# shelves_v60.net
KiCad netlist of a schematic drawn in EAGLE
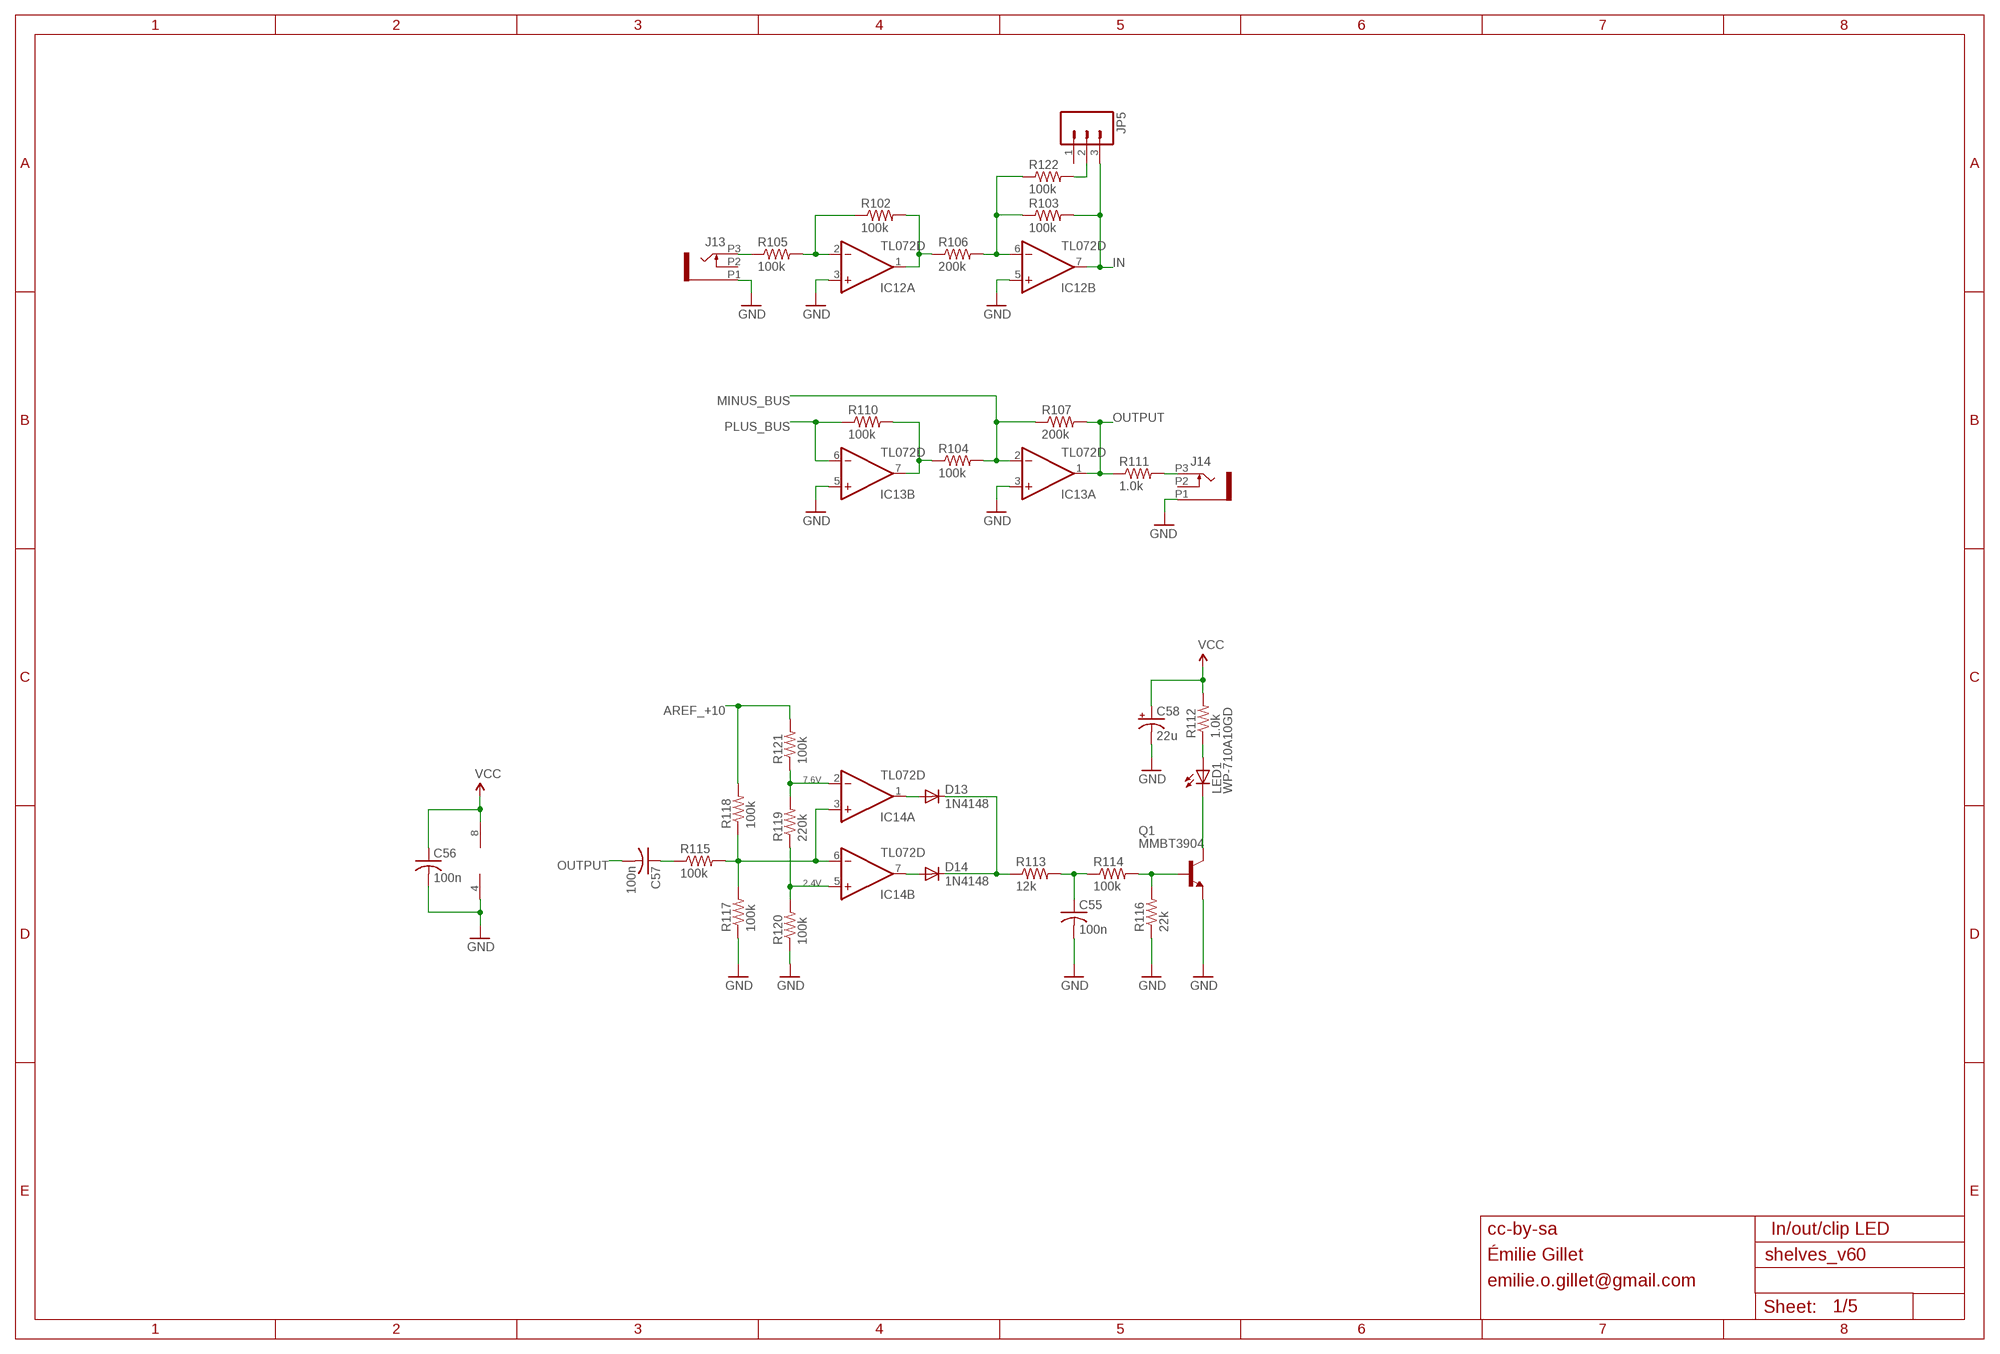
[diagram p0: schematic, sheet 1]
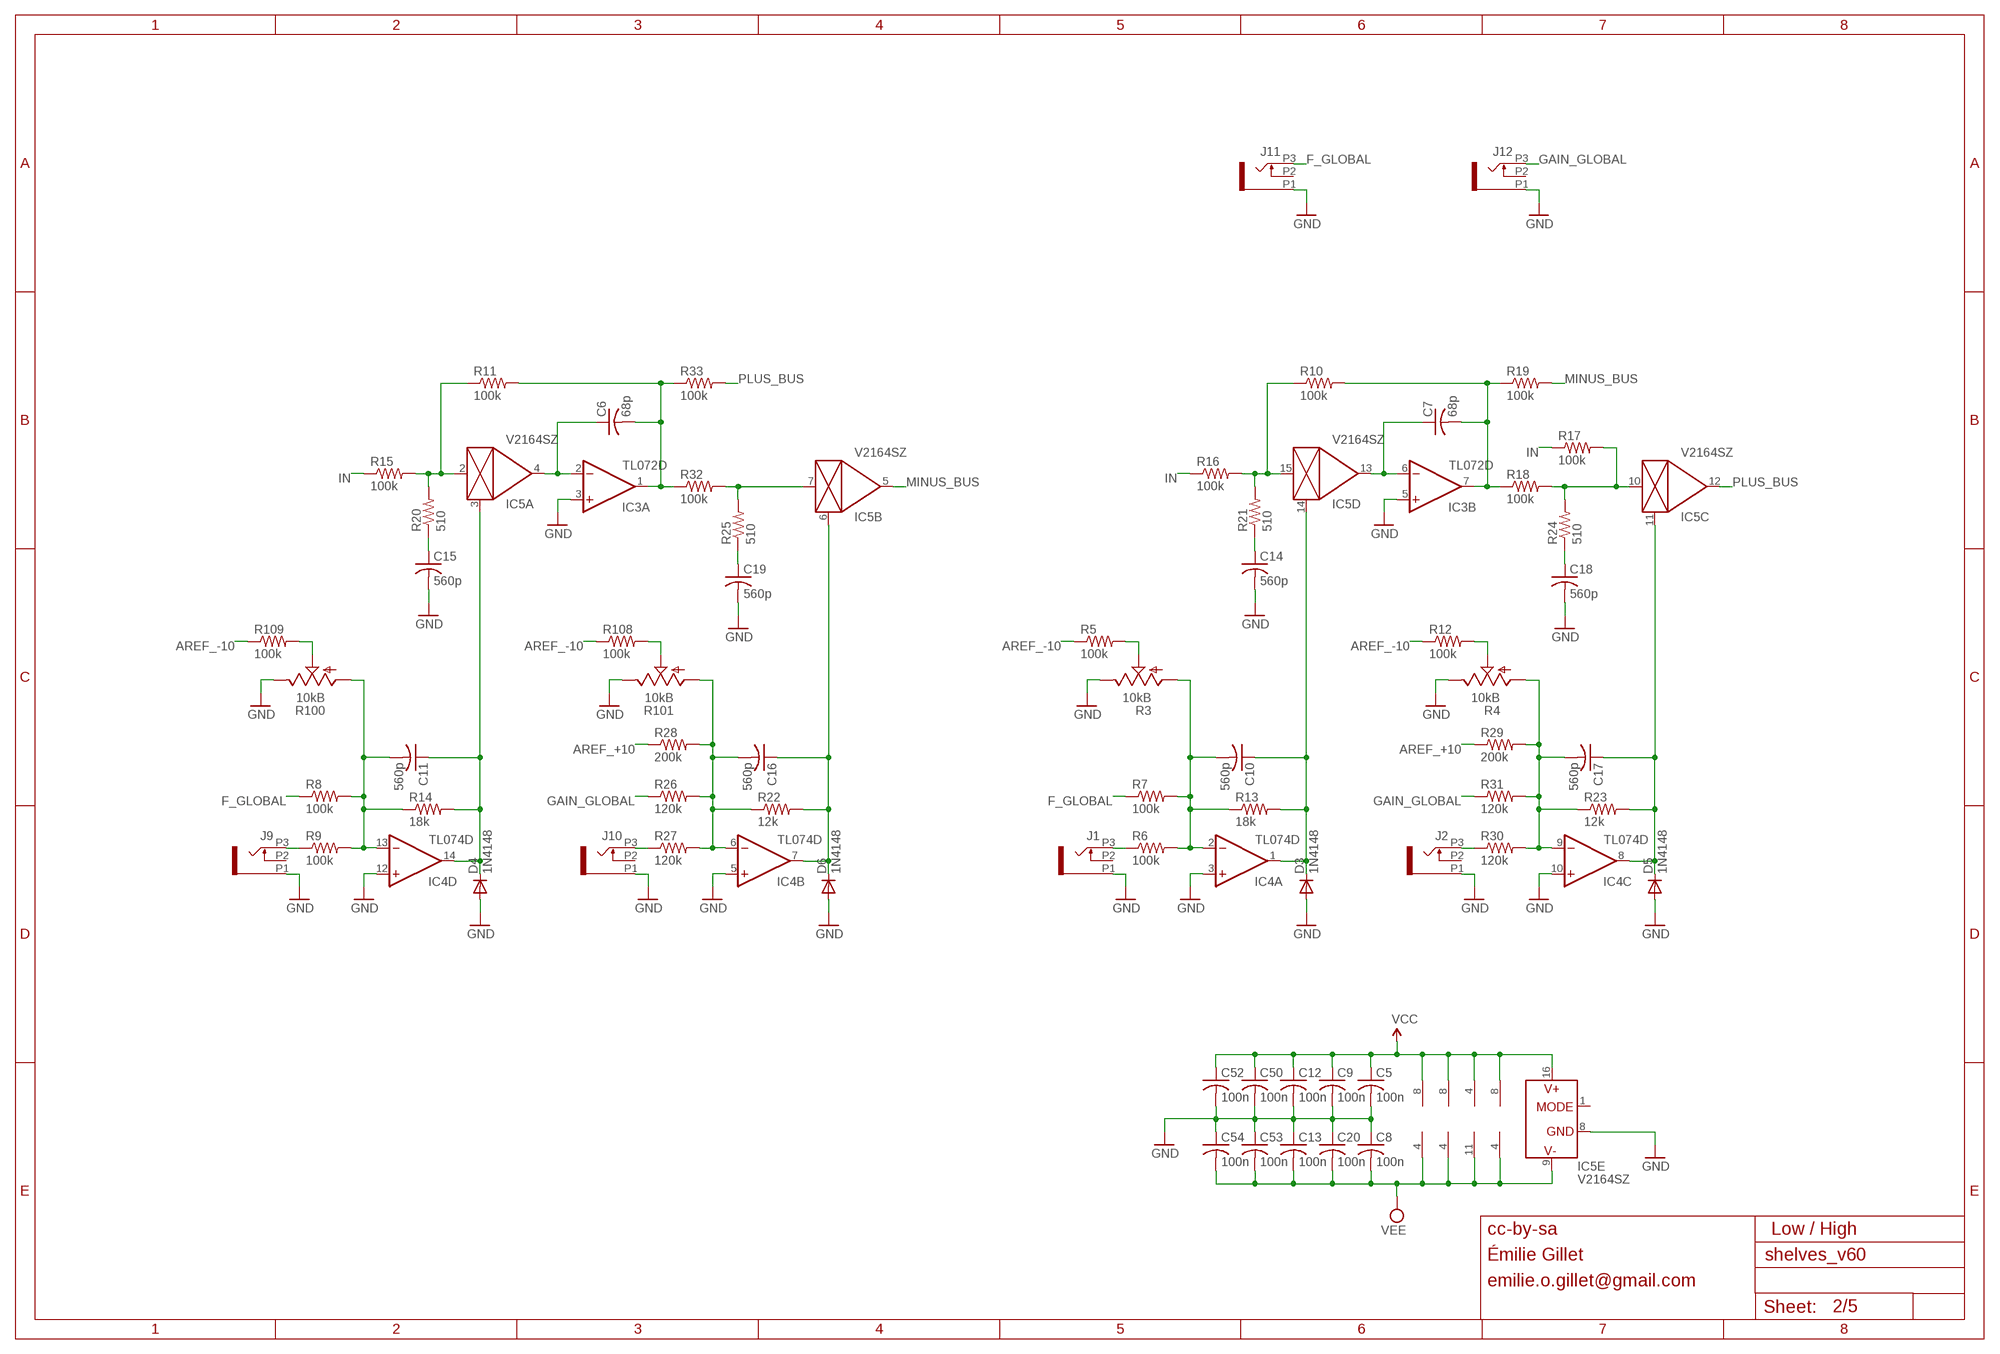
[diagram p1: schematic, sheet 2]
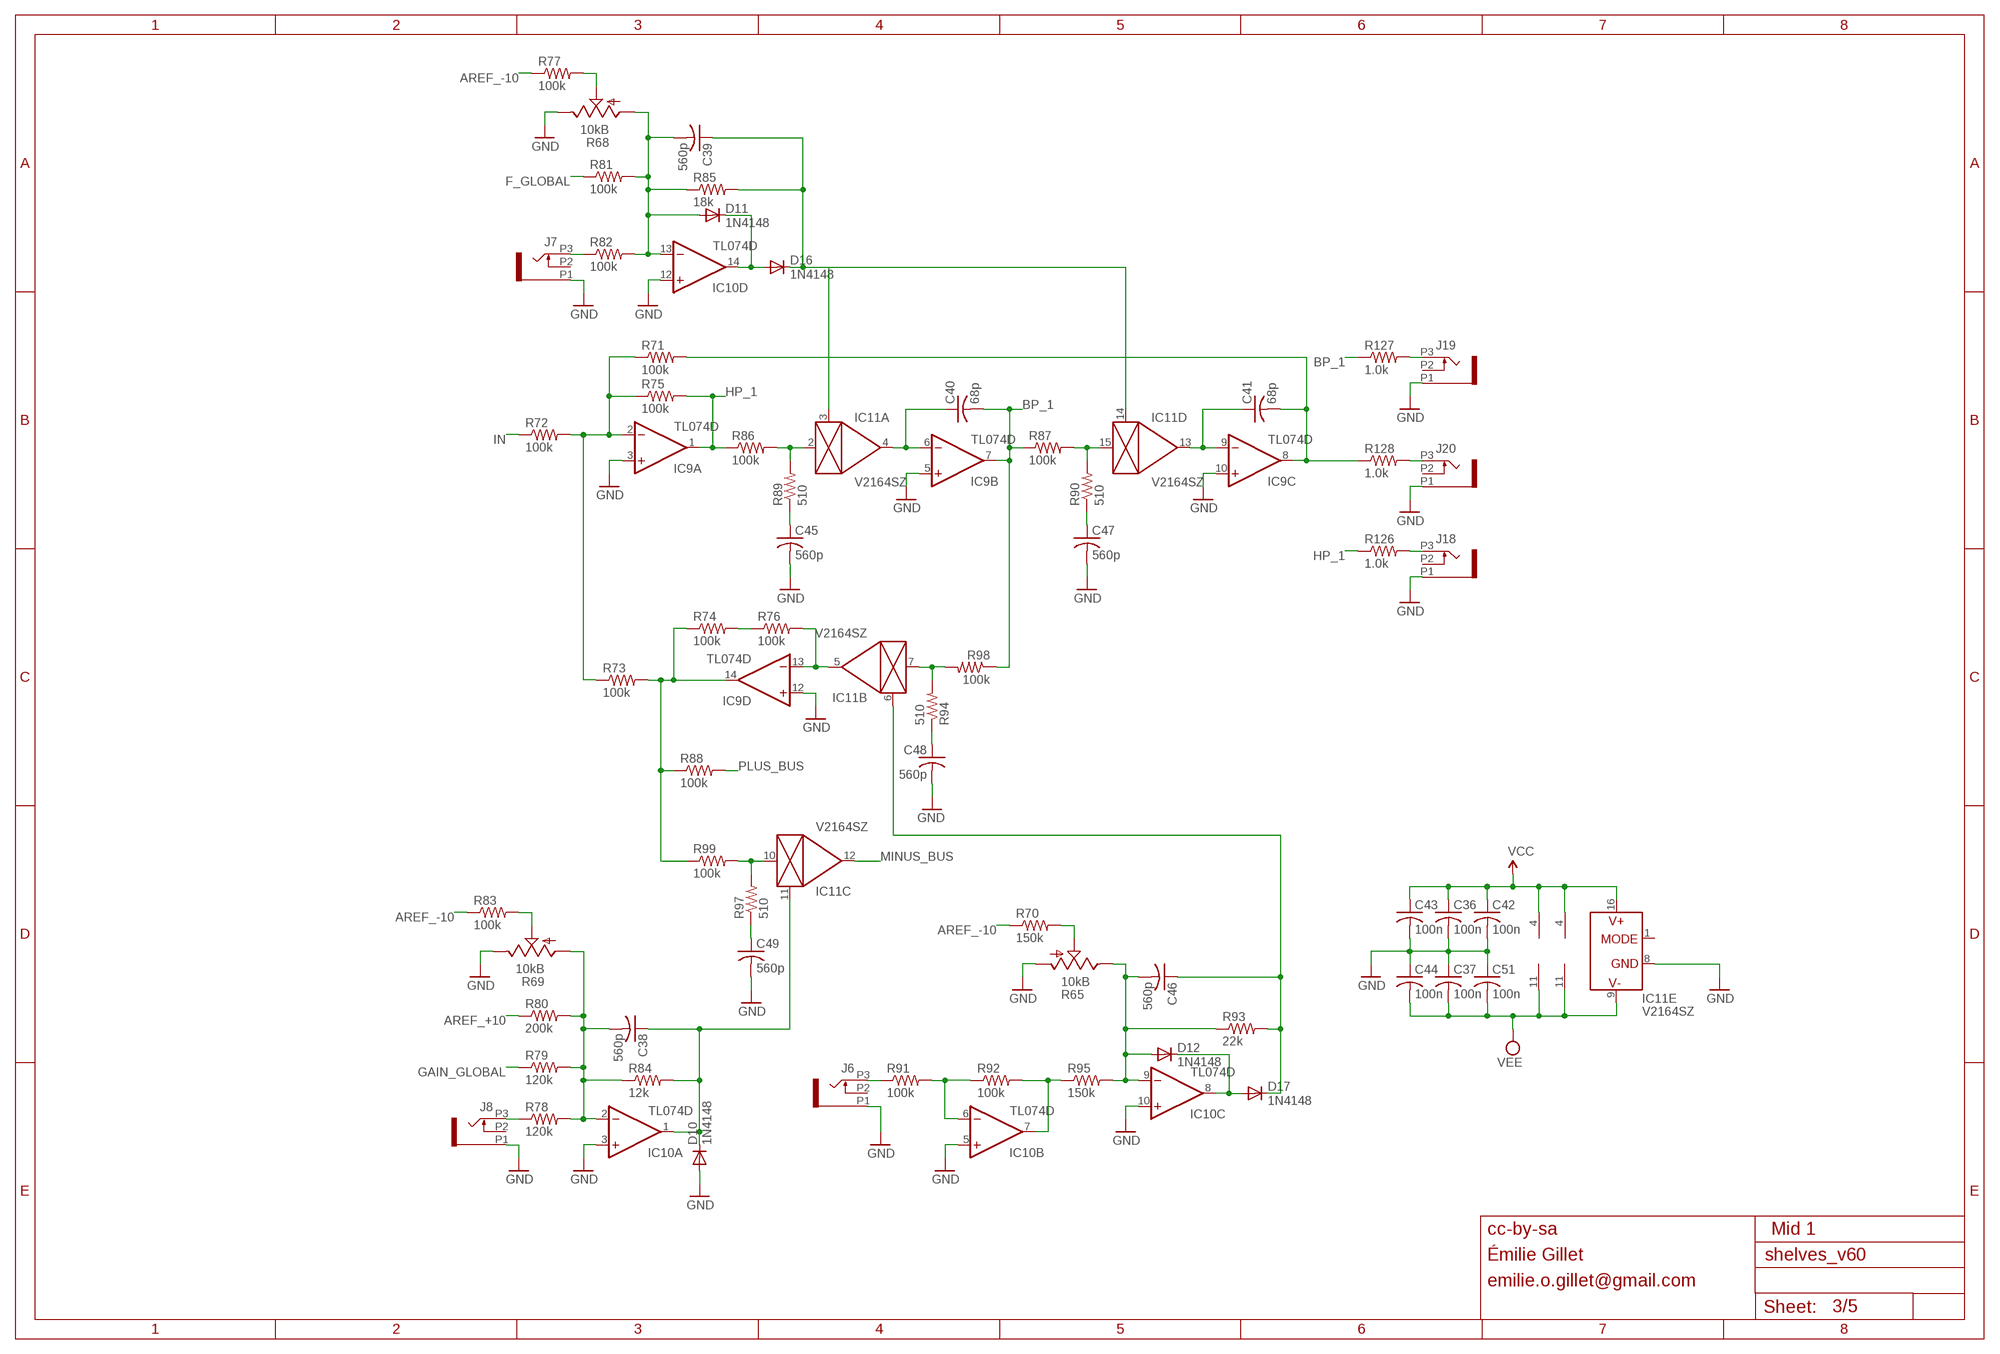
[diagram p2: schematic, sheet 3]
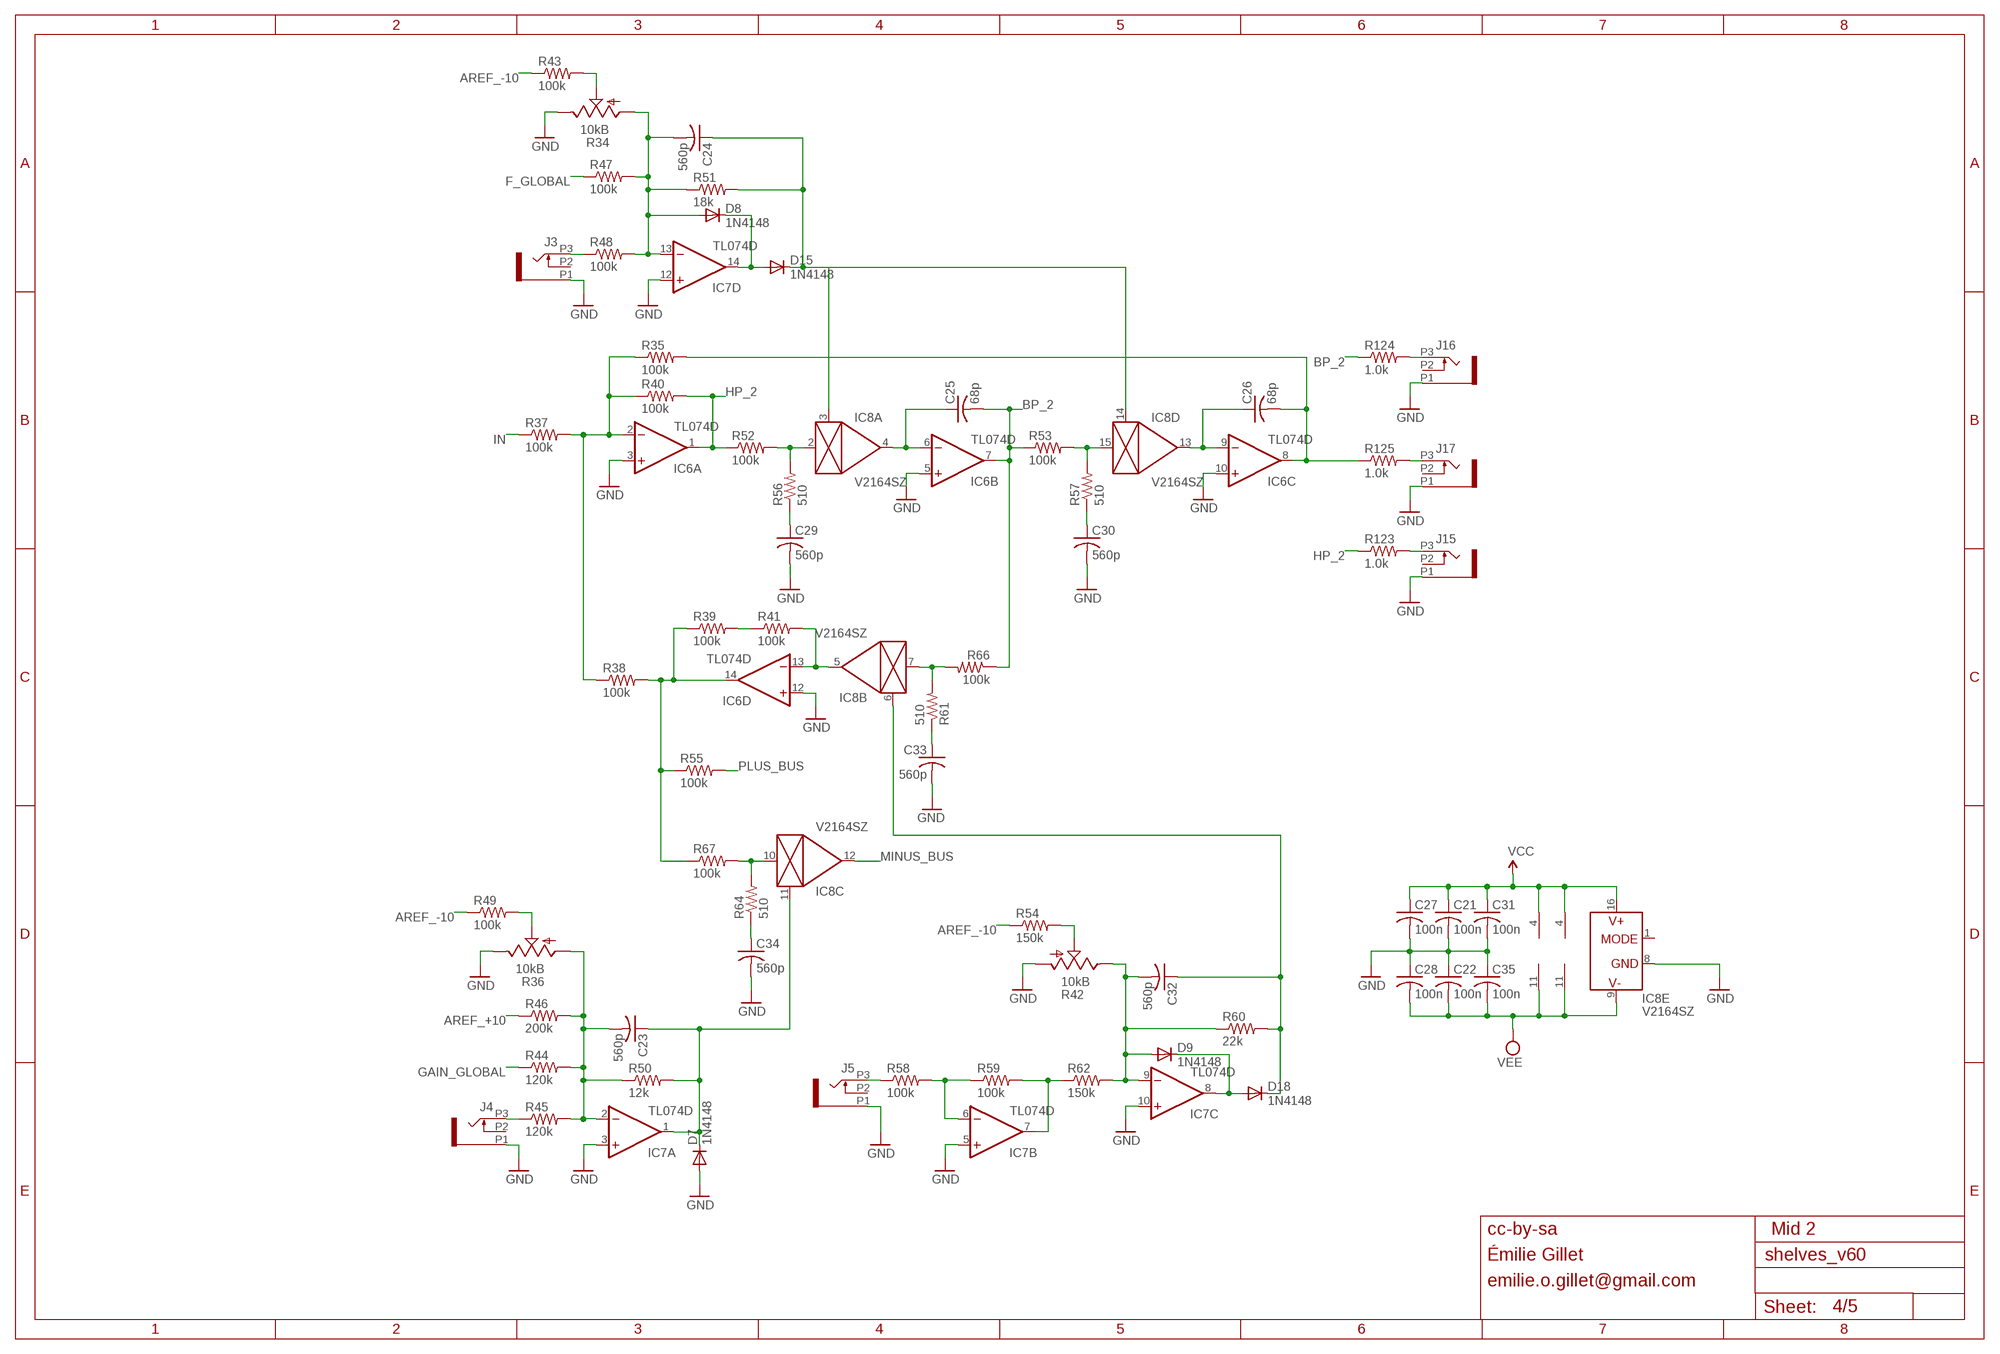
[diagram p3: schematic, sheet 4]
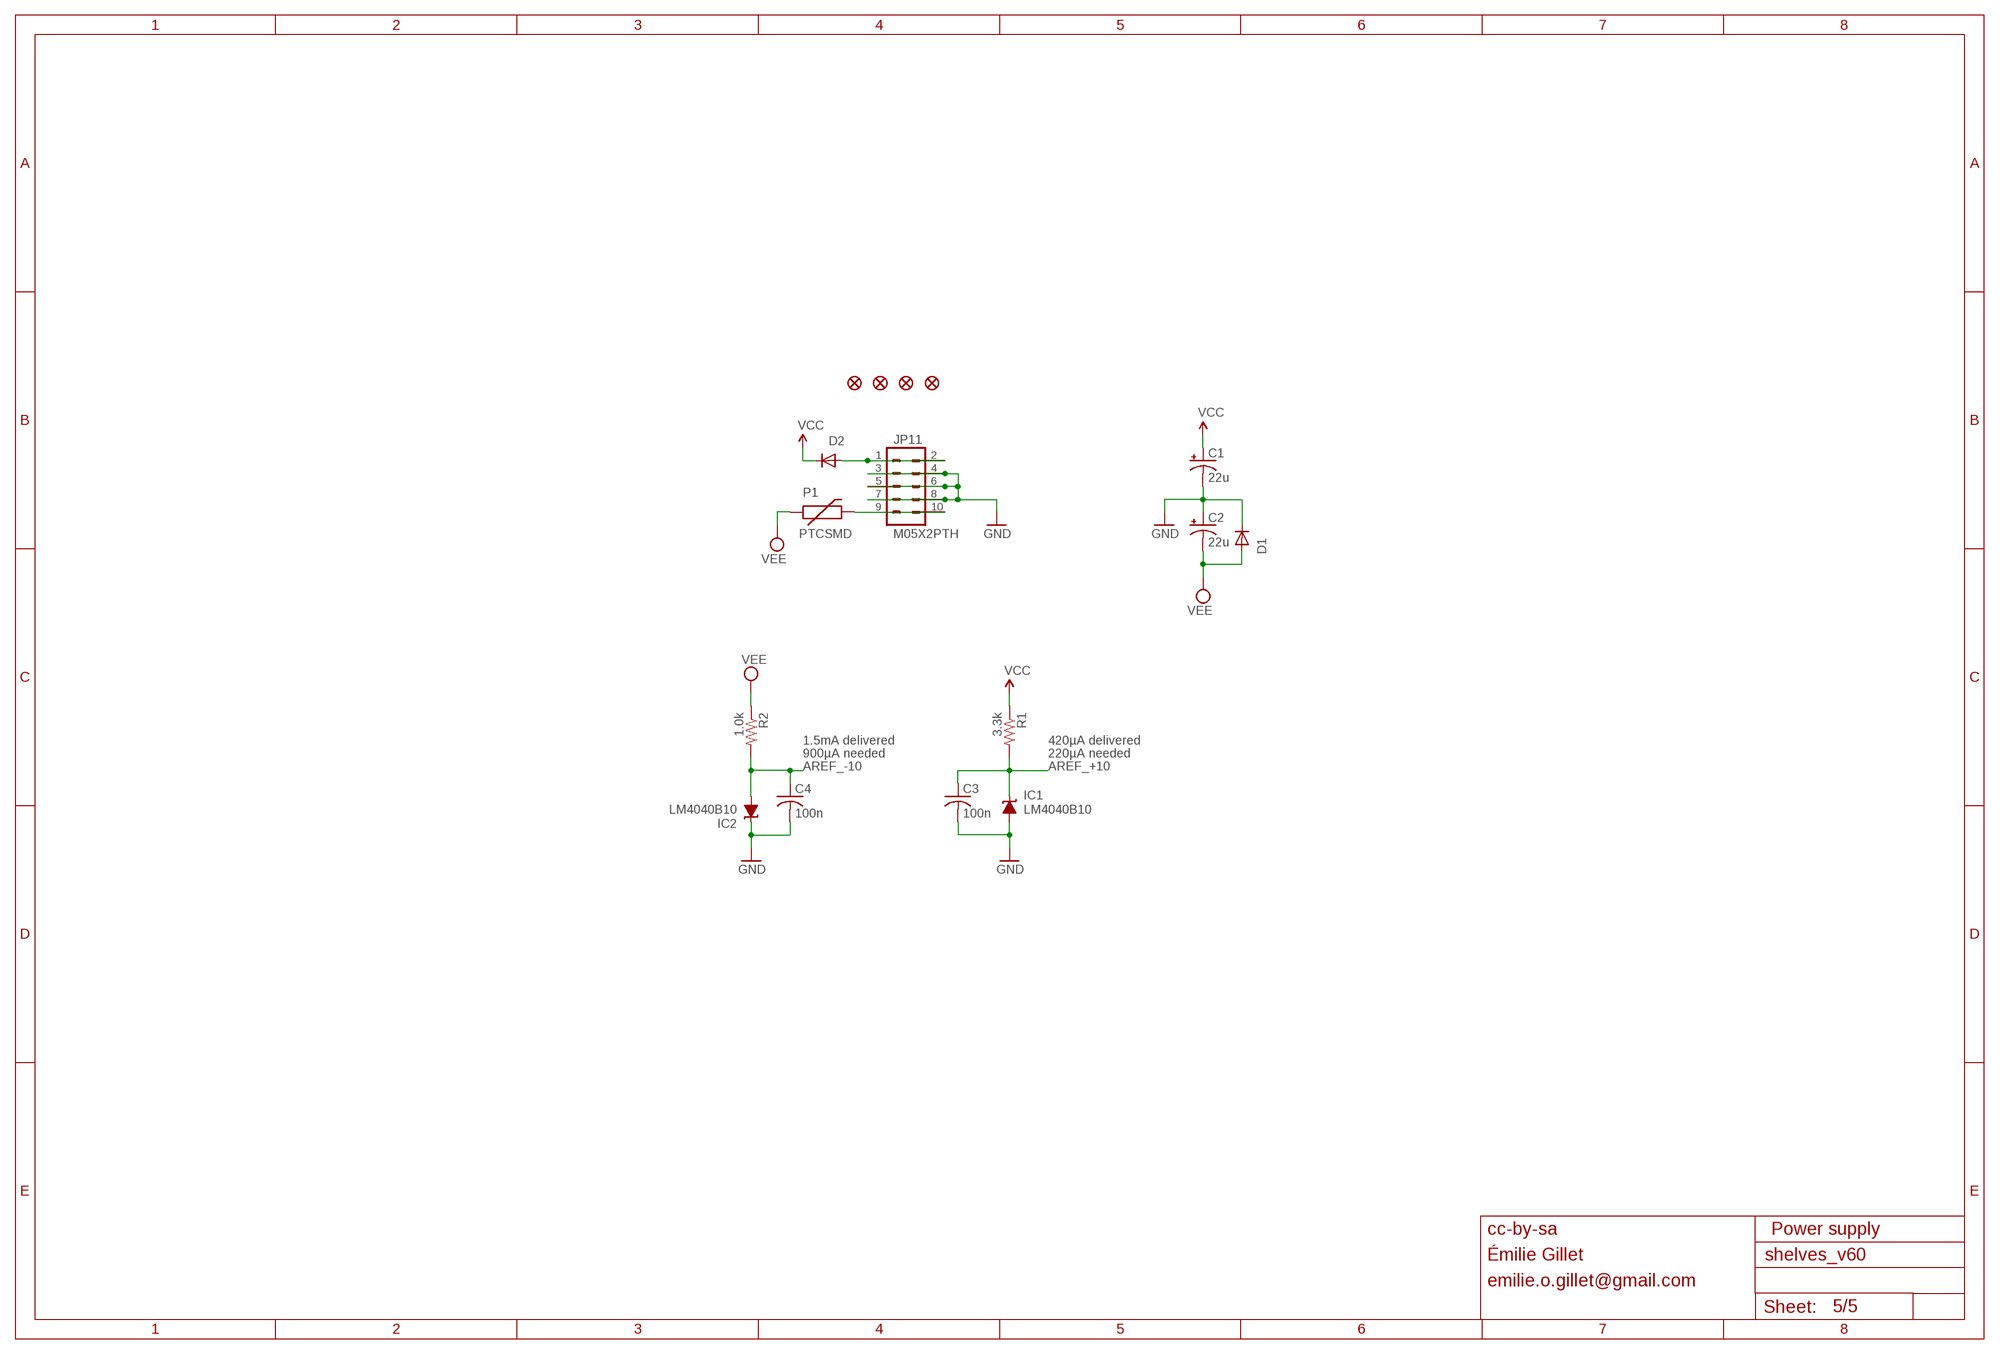
[diagram p4: schematic, sheet 5]

(export (version "E")
  (design (tool "Eeschema 10.0.6"))
  (components
    (comp (ref "C36")
      (value "100n")
      (footprint "eagle-import:C0603")
      (libsource (lib "eagle-import") (part "C-USC0603"))
    )
    (comp (ref "C37")
      (value "100n")
      (footprint "eagle-import:C0603")
      (libsource (lib "eagle-import") (part "C-USC0603"))
    )
    (comp (ref "C38")
      (value "560p")
      (footprint "eagle-import:C0603")
      (libsource (lib "eagle-import") (part "C-USC0603"))
    )
    (comp (ref "C39")
      (value "560p")
      (footprint "eagle-import:C0603")
      (libsource (lib "eagle-import") (part "C-USC0603"))
    )
    (comp (ref "C40")
      (value "68p")
      (footprint "eagle-import:C0603")
      (libsource (lib "eagle-import") (part "C-USC0603"))
    )
    (comp (ref "C41")
      (value "68p")
      (footprint "eagle-import:C0603")
      (libsource (lib "eagle-import") (part "C-USC0603"))
    )
    (comp (ref "C42")
      (value "100n")
      (footprint "eagle-import:C0603")
      (libsource (lib "eagle-import") (part "C-USC0603"))
    )
    (comp (ref "C43")
      (value "100n")
      (footprint "eagle-import:C0603")
      (libsource (lib "eagle-import") (part "C-USC0603"))
    )
    (comp (ref "C44")
      (value "100n")
      (footprint "eagle-import:C0603")
      (libsource (lib "eagle-import") (part "C-USC0603"))
    )
    (comp (ref "C45")
      (value "560p")
      (footprint "eagle-import:C0603")
      (libsource (lib "eagle-import") (part "C-USC0603"))
    )
    (comp (ref "C46")
      (value "560p")
      (footprint "eagle-import:C0603")
      (libsource (lib "eagle-import") (part "C-USC0603"))
    )
    (comp (ref "C47")
      (value "560p")
      (footprint "eagle-import:C0603")
      (libsource (lib "eagle-import") (part "C-USC0603"))
    )
    (comp (ref "C48")
      (value "560p")
      (footprint "eagle-import:C0603")
      (libsource (lib "eagle-import") (part "C-USC0603"))
    )
    (comp (ref "C49")
      (value "560p")
      (footprint "eagle-import:C0603")
      (libsource (lib "eagle-import") (part "C-USC0603"))
    )
    (comp (ref "C51")
      (value "100n")
      (footprint "eagle-import:C0603")
      (libsource (lib "eagle-import") (part "C-USC0603"))
    )
    (comp (ref "D10")
      (value "1N4148")
      (footprint "eagle-import:SOD323-W")
      (libsource (lib "eagle-import") (part "DIODE-SOD323-W"))
    )
    (comp (ref "D11")
      (value "1N4148")
      (footprint "eagle-import:SOD323-W")
      (libsource (lib "eagle-import") (part "DIODE-SOD323-W"))
    )
    (comp (ref "D12")
      (value "1N4148")
      (footprint "eagle-import:SOD323-W")
      (libsource (lib "eagle-import") (part "DIODE-SOD323-W"))
    )
    (comp (ref "D16")
      (value "1N4148")
      (footprint "eagle-import:SOD323-W")
      (libsource (lib "eagle-import") (part "DIODE-SOD323-W"))
    )
    (comp (ref "D17")
      (value "1N4148")
      (footprint "eagle-import:SOD323-W")
      (libsource (lib "eagle-import") (part "DIODE-SOD323-W"))
    )
    (comp (ref "IC9")
      (value "TL074D")
      (footprint "eagle-import:SO14")
      (libsource (lib "eagle-import") (part "TL074D"))
    )
    (comp (ref "IC10")
      (value "TL074D")
      (footprint "eagle-import:SO14")
      (libsource (lib "eagle-import") (part "TL074D"))
    )
    (comp (ref "IC11")
      (value "V2164SZ")
      (footprint "eagle-import:SOIC16N")
      (libsource (lib "eagle-import") (part "SSM2164S"))
    )
    (comp (ref "J6")
      (value "PJ301_THONKICONN6")
      (footprint "eagle-import:WQP_PJ_301M6")
      (libsource (lib "eagle-import") (part "PJ301_THONKICONN6"))
    )
    (comp (ref "J7")
      (value "PJ301_THONKICONN6")
      (footprint "eagle-import:WQP_PJ_301M6")
      (libsource (lib "eagle-import") (part "PJ301_THONKICONN6"))
    )
    (comp (ref "J8")
      (value "PJ301_THONKICONN6")
      (footprint "eagle-import:WQP_PJ_301M6")
      (libsource (lib "eagle-import") (part "PJ301_THONKICONN6"))
    )
    (comp (ref "J18")
      (value "PJ301_THONKICONN6")
      (footprint "eagle-import:WQP_PJ_301M6")
      (libsource (lib "eagle-import") (part "PJ301_THONKICONN6"))
    )
    (comp (ref "J19")
      (value "PJ301_THONKICONN6")
      (footprint "eagle-import:WQP_PJ_301M6")
      (libsource (lib "eagle-import") (part "PJ301_THONKICONN6"))
    )
    (comp (ref "J20")
      (value "PJ301_THONKICONN6")
      (footprint "eagle-import:WQP_PJ_301M6")
      (libsource (lib "eagle-import") (part "PJ301_THONKICONN6"))
    )
    (comp (ref "R65")
      (value "10kB")
      (footprint "eagle-import:ALPS_POT_VERTICAL")
      (libsource (lib "eagle-import") (part "POT_USVERTICAL"))
    )
    (comp (ref "R68")
      (value "10kB")
      (footprint "eagle-import:ALPS_POT_VERTICAL_PS")
      (libsource (lib "eagle-import") (part "POT_USVERTICAL_PS"))
    )
    (comp (ref "R69")
      (value "10kB")
      (footprint "eagle-import:ALPS_POT_VERTICAL_PS")
      (libsource (lib "eagle-import") (part "POT_USVERTICAL_PS"))
    )
    (comp (ref "R70")
      (value "150k")
      (footprint "eagle-import:R0603")
      (libsource (lib "eagle-import") (part "R-US_R0603"))
    )
    (comp (ref "R71")
      (value "100k")
      (footprint "eagle-import:R0603")
      (libsource (lib "eagle-import") (part "R-US_R0603"))
    )
    (comp (ref "R72")
      (value "100k")
      (footprint "eagle-import:R0603")
      (libsource (lib "eagle-import") (part "R-US_R0603"))
    )
    (comp (ref "R73")
      (value "100k")
      (footprint "eagle-import:R0603")
      (libsource (lib "eagle-import") (part "R-US_R0603"))
    )
    (comp (ref "R74")
      (value "100k")
      (footprint "eagle-import:R0603")
      (libsource (lib "eagle-import") (part "R-US_R0603"))
    )
    (comp (ref "R75")
      (value "100k")
      (footprint "eagle-import:R0603")
      (libsource (lib "eagle-import") (part "R-US_R0603"))
    )
    (comp (ref "R76")
      (value "100k")
      (footprint "eagle-import:R0603")
      (libsource (lib "eagle-import") (part "R-US_R0603"))
    )
    (comp (ref "R77")
      (value "100k")
      (footprint "eagle-import:R0603")
      (libsource (lib "eagle-import") (part "R-US_R0603"))
    )
    (comp (ref "R78")
      (value "120k")
      (footprint "eagle-import:R0603")
      (libsource (lib "eagle-import") (part "R-US_R0603"))
    )
    (comp (ref "R79")
      (value "120k")
      (footprint "eagle-import:R0603")
      (libsource (lib "eagle-import") (part "R-US_R0603"))
    )
    (comp (ref "R80")
      (value "200k")
      (footprint "eagle-import:R0603")
      (libsource (lib "eagle-import") (part "R-US_R0603"))
    )
    (comp (ref "R81")
      (value "100k")
      (footprint "eagle-import:R0603")
      (libsource (lib "eagle-import") (part "R-US_R0603"))
    )
    (comp (ref "R82")
      (value "100k")
      (footprint "eagle-import:R0603")
      (libsource (lib "eagle-import") (part "R-US_R0603"))
    )
    (comp (ref "R83")
      (value "100k")
      (footprint "eagle-import:R0603")
      (libsource (lib "eagle-import") (part "R-US_R0603"))
    )
    (comp (ref "R84")
      (value "12k")
      (footprint "eagle-import:R0603")
      (libsource (lib "eagle-import") (part "R-US_R0603"))
    )
    (comp (ref "R85")
      (value "18k")
      (footprint "eagle-import:R0603")
      (libsource (lib "eagle-import") (part "R-US_R0603"))
    )
    (comp (ref "R86")
      (value "100k")
      (footprint "eagle-import:R0603")
      (libsource (lib "eagle-import") (part "R-US_R0603"))
    )
    (comp (ref "R87")
      (value "100k")
      (footprint "eagle-import:R0603")
      (libsource (lib "eagle-import") (part "R-US_R0603"))
    )
    (comp (ref "R88")
      (value "100k")
      (footprint "eagle-import:R0603")
      (libsource (lib "eagle-import") (part "R-US_R0603"))
    )
    (comp (ref "R89")
      (value "510")
      (footprint "eagle-import:R0603")
      (libsource (lib "eagle-import") (part "R-US_R0603"))
    )
    (comp (ref "R90")
      (value "510")
      (footprint "eagle-import:R0603")
      (libsource (lib "eagle-import") (part "R-US_R0603"))
    )
    (comp (ref "R91")
      (value "100k")
      (footprint "eagle-import:R0603")
      (libsource (lib "eagle-import") (part "R-US_R0603"))
    )
    (comp (ref "R92")
      (value "100k")
      (footprint "eagle-import:R0603")
      (libsource (lib "eagle-import") (part "R-US_R0603"))
    )
    (comp (ref "R93")
      (value "22k")
      (footprint "eagle-import:R0603")
      (libsource (lib "eagle-import") (part "R-US_R0603"))
    )
    (comp (ref "R94")
      (value "510")
      (footprint "eagle-import:R0603")
      (libsource (lib "eagle-import") (part "R-US_R0603"))
    )
    (comp (ref "R95")
      (value "150k")
      (footprint "eagle-import:R0603")
      (libsource (lib "eagle-import") (part "R-US_R0603"))
    )
    (comp (ref "R97")
      (value "510")
      (footprint "eagle-import:R0603")
      (libsource (lib "eagle-import") (part "R-US_R0603"))
    )
    (comp (ref "R98")
      (value "100k")
      (footprint "eagle-import:R0603")
      (libsource (lib "eagle-import") (part "R-US_R0603"))
    )
    (comp (ref "R99")
      (value "100k")
      (footprint "eagle-import:R0603")
      (libsource (lib "eagle-import") (part "R-US_R0603"))
    )
    (comp (ref "R126")
      (value "1.0k")
      (footprint "eagle-import:R0603")
      (libsource (lib "eagle-import") (part "R-US_R0603"))
    )
    (comp (ref "R127")
      (value "1.0k")
      (footprint "eagle-import:R0603")
      (libsource (lib "eagle-import") (part "R-US_R0603"))
    )
    (comp (ref "R128")
      (value "1.0k")
      (footprint "eagle-import:R0603")
      (libsource (lib "eagle-import") (part "R-US_R0603"))
    )
    (comp (ref "C1")
      (value "22u")
      (footprint "eagle-import:PANASONIC_C")
      (libsource (lib "eagle-import") (part "CPOL-USC"))
    )
    (comp (ref "C2")
      (value "22u")
      (footprint "eagle-import:PANASONIC_C")
      (libsource (lib "eagle-import") (part "CPOL-USC"))
    )
    (comp (ref "C3")
      (value "100n")
      (footprint "eagle-import:C0603")
      (libsource (lib "eagle-import") (part "C-USC0603"))
    )
    (comp (ref "C4")
      (value "100n")
      (footprint "eagle-import:C0603")
      (libsource (lib "eagle-import") (part "C-USC0603"))
    )
    (comp (ref "D1")
      (value "1N5819HW")
      (footprint "eagle-import:SOD123")
      (libsource (lib "eagle-import") (part "DIODE-SOD123"))
    )
    (comp (ref "D2")
      (value "1N5819HW")
      (footprint "eagle-import:SOD123")
      (libsource (lib "eagle-import") (part "DIODE-SOD123"))
    )
    (comp (ref "IC1")
      (value "LM4040B10")
      (footprint "eagle-import:DBZ_R-PDSO-G3")
      (libsource (lib "eagle-import") (part "LM4041DBZB12"))
    )
    (comp (ref "IC2")
      (value "LM4040B10")
      (footprint "eagle-import:DBZ_R-PDSO-G3")
      (libsource (lib "eagle-import") (part "LM4041DBZB12"))
    )
    (comp (ref "JP1")
      (value "FIDUCIAL1X2")
      (footprint "eagle-import:FIDUCIAL-1X2")
      (libsource (lib "eagle-import") (part "FIDUCIAL1X2"))
    )
    (comp (ref "JP2")
      (value "FIDUCIAL1X2")
      (footprint "eagle-import:FIDUCIAL-1X2")
      (libsource (lib "eagle-import") (part "FIDUCIAL1X2"))
    )
    (comp (ref "JP3")
      (value "FIDUCIAL1X2")
      (footprint "eagle-import:FIDUCIAL-1X2")
      (libsource (lib "eagle-import") (part "FIDUCIAL1X2"))
    )
    (comp (ref "JP4")
      (value "FIDUCIAL1X2")
      (footprint "eagle-import:FIDUCIAL-1X2")
      (libsource (lib "eagle-import") (part "FIDUCIAL1X2"))
    )
    (comp (ref "JP11")
      (value "M05X2PTH")
      (footprint "eagle-import:AVR_ICSP")
      (libsource (lib "eagle-import") (part "M05X2PTH"))
    )
    (comp (ref "P1")
      (value "PTCSMD")
      (footprint "eagle-import:PTC-1206")
      (libsource (lib "eagle-import") (part "PTCSMD"))
    )
    (comp (ref "R1")
      (value "3.3k")
      (footprint "eagle-import:R0603")
      (libsource (lib "eagle-import") (part "R-US_R0603"))
    )
    (comp (ref "R2")
      (value "1.0k")
      (footprint "eagle-import:R0603")
      (libsource (lib "eagle-import") (part "R-US_R0603"))
    )
    (comp (ref "C55")
      (value "100n")
      (footprint "eagle-import:C0603")
      (libsource (lib "eagle-import") (part "C-USC0603"))
    )
    (comp (ref "C56")
      (value "100n")
      (footprint "eagle-import:C0603")
      (libsource (lib "eagle-import") (part "C-USC0603"))
    )
    (comp (ref "C57")
      (value "100n")
      (footprint "eagle-import:C0603")
      (libsource (lib "eagle-import") (part "C-USC0603"))
    )
    (comp (ref "C58")
      (value "22u")
      (footprint "eagle-import:PANASONIC_C")
      (libsource (lib "eagle-import") (part "CPOL-USC"))
    )
    (comp (ref "D13")
      (value "1N4148")
      (footprint "eagle-import:SOD323-W")
      (libsource (lib "eagle-import") (part "DIODE-SOD323-W"))
    )
    (comp (ref "D14")
      (value "1N4148")
      (footprint "eagle-import:SOD323-W")
      (libsource (lib "eagle-import") (part "DIODE-SOD323-W"))
    )
    (comp (ref "IC12")
      (value "TL072D")
      (footprint "eagle-import:SO08")
      (libsource (lib "eagle-import") (part "TL072D"))
    )
    (comp (ref "IC13")
      (value "TL072D")
      (footprint "eagle-import:SO08")
      (libsource (lib "eagle-import") (part "TL072D"))
    )
    (comp (ref "IC14")
      (value "TL072D")
      (footprint "eagle-import:SO08")
      (libsource (lib "eagle-import") (part "TL072D"))
    )
    (comp (ref "J13")
      (value "PJ301_THONKICONN6")
      (footprint "eagle-import:WQP_PJ_301M6")
      (libsource (lib "eagle-import") (part "PJ301_THONKICONN6"))
    )
    (comp (ref "J14")
      (value "PJ301_THONKICONN6")
      (footprint "eagle-import:WQP_PJ_301M6")
      (libsource (lib "eagle-import") (part "PJ301_THONKICONN6"))
    )
    (comp (ref "JP5")
      (value "M03PTH")
      (footprint "eagle-import:1X03")
      (libsource (lib "eagle-import") (part "M03PTH"))
    )
    (comp (ref "LED1")
      (value "WP-710A10GD")
      (footprint "eagle-import:LED3MM")
      (libsource (lib "eagle-import") (part "LED3MM"))
    )
    (comp (ref "Q1")
      (value "MMBT3904")
      (footprint "eagle-import:SOT23-BEC")
      (libsource (lib "eagle-import") (part "-NPN-SOT23-BECMMBT3904LT1"))
    )
    (comp (ref "R102")
      (value "100k")
      (footprint "eagle-import:R0603")
      (libsource (lib "eagle-import") (part "R-US_R0603"))
    )
    (comp (ref "R103")
      (value "100k")
      (footprint "eagle-import:R0603")
      (libsource (lib "eagle-import") (part "R-US_R0603"))
    )
    (comp (ref "R104")
      (value "100k")
      (footprint "eagle-import:R0603")
      (libsource (lib "eagle-import") (part "R-US_R0603"))
    )
    (comp (ref "R105")
      (value "100k")
      (footprint "eagle-import:R0603")
      (libsource (lib "eagle-import") (part "R-US_R0603"))
    )
    (comp (ref "R106")
      (value "200k")
      (footprint "eagle-import:R0603")
      (libsource (lib "eagle-import") (part "R-US_R0603"))
    )
    (comp (ref "R107")
      (value "200k")
      (footprint "eagle-import:R0603")
      (libsource (lib "eagle-import") (part "R-US_R0603"))
    )
    (comp (ref "R110")
      (value "100k")
      (footprint "eagle-import:R0603")
      (libsource (lib "eagle-import") (part "R-US_R0603"))
    )
    (comp (ref "R111")
      (value "1.0k")
      (footprint "eagle-import:R0603")
      (libsource (lib "eagle-import") (part "R-US_R0603"))
    )
    (comp (ref "R112")
      (value "1.0k")
      (footprint "eagle-import:R0603")
      (libsource (lib "eagle-import") (part "R-US_R0603"))
    )
    (comp (ref "R113")
      (value "12k")
      (footprint "eagle-import:R0603")
      (libsource (lib "eagle-import") (part "R-US_R0603"))
    )
    (comp (ref "R114")
      (value "100k")
      (footprint "eagle-import:R0603")
      (libsource (lib "eagle-import") (part "R-US_R0603"))
    )
    (comp (ref "R115")
      (value "100k")
      (footprint "eagle-import:R0603")
      (libsource (lib "eagle-import") (part "R-US_R0603"))
    )
    (comp (ref "R116")
      (value "22k")
      (footprint "eagle-import:R0603")
      (libsource (lib "eagle-import") (part "R-US_R0603"))
    )
    (comp (ref "R117")
      (value "100k")
      (footprint "eagle-import:R0603")
      (libsource (lib "eagle-import") (part "R-US_R0603"))
    )
    (comp (ref "R118")
      (value "100k")
      (footprint "eagle-import:R0603")
      (libsource (lib "eagle-import") (part "R-US_R0603"))
    )
    (comp (ref "R119")
      (value "220k")
      (footprint "eagle-import:R0603")
      (libsource (lib "eagle-import") (part "R-US_R0603"))
    )
    (comp (ref "R120")
      (value "100k")
      (footprint "eagle-import:R0603")
      (libsource (lib "eagle-import") (part "R-US_R0603"))
    )
    (comp (ref "R121")
      (value "100k")
      (footprint "eagle-import:R0603")
      (libsource (lib "eagle-import") (part "R-US_R0603"))
    )
    (comp (ref "R122")
      (value "100k")
      (footprint "eagle-import:R0603")
      (libsource (lib "eagle-import") (part "R-US_R0603"))
    )
    (comp (ref "C5")
      (value "100n")
      (footprint "eagle-import:C0603")
      (libsource (lib "eagle-import") (part "C-USC0603"))
    )
    (comp (ref "C6")
      (value "68p")
      (footprint "eagle-import:C0603")
      (libsource (lib "eagle-import") (part "C-USC0603"))
    )
    (comp (ref "C7")
      (value "68p")
      (footprint "eagle-import:C0603")
      (libsource (lib "eagle-import") (part "C-USC0603"))
    )
    (comp (ref "C8")
      (value "100n")
      (footprint "eagle-import:C0603")
      (libsource (lib "eagle-import") (part "C-USC0603"))
    )
    (comp (ref "C9")
      (value "100n")
      (footprint "eagle-import:C0603")
      (libsource (lib "eagle-import") (part "C-USC0603"))
    )
    (comp (ref "C10")
      (value "560p")
      (footprint "eagle-import:C0603")
      (libsource (lib "eagle-import") (part "C-USC0603"))
    )
    (comp (ref "C11")
      (value "560p")
      (footprint "eagle-import:C0603")
      (libsource (lib "eagle-import") (part "C-USC0603"))
    )
    (comp (ref "C12")
      (value "100n")
      (footprint "eagle-import:C0603")
      (libsource (lib "eagle-import") (part "C-USC0603"))
    )
    (comp (ref "C13")
      (value "100n")
      (footprint "eagle-import:C0603")
      (libsource (lib "eagle-import") (part "C-USC0603"))
    )
    (comp (ref "C14")
      (value "560p")
      (footprint "eagle-import:C0603")
      (libsource (lib "eagle-import") (part "C-USC0603"))
    )
    (comp (ref "C15")
      (value "560p")
      (footprint "eagle-import:C0603")
      (libsource (lib "eagle-import") (part "C-USC0603"))
    )
    (comp (ref "C16")
      (value "560p")
      (footprint "eagle-import:C0603")
      (libsource (lib "eagle-import") (part "C-USC0603"))
    )
    (comp (ref "C17")
      (value "560p")
      (footprint "eagle-import:C0603")
      (libsource (lib "eagle-import") (part "C-USC0603"))
    )
    (comp (ref "C18")
      (value "560p")
      (footprint "eagle-import:C0603")
      (libsource (lib "eagle-import") (part "C-USC0603"))
    )
    (comp (ref "C19")
      (value "560p")
      (footprint "eagle-import:C0603")
      (libsource (lib "eagle-import") (part "C-USC0603"))
    )
    (comp (ref "C20")
      (value "100n")
      (footprint "eagle-import:C0603")
      (libsource (lib "eagle-import") (part "C-USC0603"))
    )
    (comp (ref "C50")
      (value "100n")
      (footprint "eagle-import:C0603")
      (libsource (lib "eagle-import") (part "C-USC0603"))
    )
    (comp (ref "C52")
      (value "100n")
      (footprint "eagle-import:C0603")
      (libsource (lib "eagle-import") (part "C-USC0603"))
    )
    (comp (ref "C53")
      (value "100n")
      (footprint "eagle-import:C0603")
      (libsource (lib "eagle-import") (part "C-USC0603"))
    )
    (comp (ref "C54")
      (value "100n")
      (footprint "eagle-import:C0603")
      (libsource (lib "eagle-import") (part "C-USC0603"))
    )
    (comp (ref "D3")
      (value "1N4148")
      (footprint "eagle-import:SOD323-W")
      (libsource (lib "eagle-import") (part "DIODE-SOD323-W"))
    )
    (comp (ref "D4")
      (value "1N4148")
      (footprint "eagle-import:SOD323-W")
      (libsource (lib "eagle-import") (part "DIODE-SOD323-W"))
    )
    (comp (ref "D5")
      (value "1N4148")
      (footprint "eagle-import:SOD323-W")
      (libsource (lib "eagle-import") (part "DIODE-SOD323-W"))
    )
    (comp (ref "D6")
      (value "1N4148")
      (footprint "eagle-import:SOD323-W")
      (libsource (lib "eagle-import") (part "DIODE-SOD323-W"))
    )
    (comp (ref "IC3")
      (value "TL072D")
      (footprint "eagle-import:SO08")
      (libsource (lib "eagle-import") (part "TL072D"))
    )
    (comp (ref "IC4")
      (value "TL074D")
      (footprint "eagle-import:SO14")
      (libsource (lib "eagle-import") (part "TL074D"))
    )
    (comp (ref "IC5")
      (value "V2164SZ")
      (footprint "eagle-import:SOIC16N")
      (libsource (lib "eagle-import") (part "SSM2164S"))
    )
    (comp (ref "J1")
      (value "PJ301_THONKICONN6")
      (footprint "eagle-import:WQP_PJ_301M6")
      (libsource (lib "eagle-import") (part "PJ301_THONKICONN6"))
    )
    (comp (ref "J2")
      (value "PJ301_THONKICONN6")
      (footprint "eagle-import:WQP_PJ_301M6")
      (libsource (lib "eagle-import") (part "PJ301_THONKICONN6"))
    )
    (comp (ref "J9")
      (value "PJ301_THONKICONN6")
      (footprint "eagle-import:WQP_PJ_301M6")
      (libsource (lib "eagle-import") (part "PJ301_THONKICONN6"))
    )
    (comp (ref "J10")
      (value "PJ301_THONKICONN6")
      (footprint "eagle-import:WQP_PJ_301M6")
      (libsource (lib "eagle-import") (part "PJ301_THONKICONN6"))
    )
    (comp (ref "J11")
      (value "PJ301_THONKICONN6")
      (footprint "eagle-import:WQP_PJ_301M6")
      (libsource (lib "eagle-import") (part "PJ301_THONKICONN6"))
    )
    (comp (ref "J12")
      (value "PJ301_THONKICONN6")
      (footprint "eagle-import:WQP_PJ_301M6")
      (libsource (lib "eagle-import") (part "PJ301_THONKICONN6"))
    )
    (comp (ref "R3")
      (value "10kB")
      (footprint "eagle-import:ALPS_POT_VERTICAL_PS")
      (libsource (lib "eagle-import") (part "POT_USVERTICAL_PS"))
    )
    (comp (ref "R4")
      (value "10kB")
      (footprint "eagle-import:ALPS_POT_VERTICAL_PS")
      (libsource (lib "eagle-import") (part "POT_USVERTICAL_PS"))
    )
    (comp (ref "R5")
      (value "100k")
      (footprint "eagle-import:R0603")
      (libsource (lib "eagle-import") (part "R-US_R0603"))
    )
    (comp (ref "R6")
      (value "100k")
      (footprint "eagle-import:R0603")
      (libsource (lib "eagle-import") (part "R-US_R0603"))
    )
    (comp (ref "R7")
      (value "100k")
      (footprint "eagle-import:R0603")
      (libsource (lib "eagle-import") (part "R-US_R0603"))
    )
    (comp (ref "R8")
      (value "100k")
      (footprint "eagle-import:R0603")
      (libsource (lib "eagle-import") (part "R-US_R0603"))
    )
    (comp (ref "R9")
      (value "100k")
      (footprint "eagle-import:R0603")
      (libsource (lib "eagle-import") (part "R-US_R0603"))
    )
    (comp (ref "R10")
      (value "100k")
      (footprint "eagle-import:R0603")
      (libsource (lib "eagle-import") (part "R-US_R0603"))
    )
    (comp (ref "R11")
      (value "100k")
      (footprint "eagle-import:R0603")
      (libsource (lib "eagle-import") (part "R-US_R0603"))
    )
    (comp (ref "R12")
      (value "100k")
      (footprint "eagle-import:R0603")
      (libsource (lib "eagle-import") (part "R-US_R0603"))
    )
    (comp (ref "R13")
      (value "18k")
      (footprint "eagle-import:R0603")
      (libsource (lib "eagle-import") (part "R-US_R0603"))
    )
    (comp (ref "R14")
      (value "18k")
      (footprint "eagle-import:R0603")
      (libsource (lib "eagle-import") (part "R-US_R0603"))
    )
    (comp (ref "R15")
      (value "100k")
      (footprint "eagle-import:R0603")
      (libsource (lib "eagle-import") (part "R-US_R0603"))
    )
    (comp (ref "R16")
      (value "100k")
      (footprint "eagle-import:R0603")
      (libsource (lib "eagle-import") (part "R-US_R0603"))
    )
    (comp (ref "R17")
      (value "100k")
      (footprint "eagle-import:R0603")
      (libsource (lib "eagle-import") (part "R-US_R0603"))
    )
    (comp (ref "R18")
      (value "100k")
      (footprint "eagle-import:R0603")
      (libsource (lib "eagle-import") (part "R-US_R0603"))
    )
    (comp (ref "R19")
      (value "100k")
      (footprint "eagle-import:R0603")
      (libsource (lib "eagle-import") (part "R-US_R0603"))
    )
    (comp (ref "R20")
      (value "510")
      (footprint "eagle-import:R0603")
      (libsource (lib "eagle-import") (part "R-US_R0603"))
    )
    (comp (ref "R21")
      (value "510")
      (footprint "eagle-import:R0603")
      (libsource (lib "eagle-import") (part "R-US_R0603"))
    )
    (comp (ref "R22")
      (value "12k")
      (footprint "eagle-import:R0603")
      (libsource (lib "eagle-import") (part "R-US_R0603"))
    )
    (comp (ref "R23")
      (value "12k")
      (footprint "eagle-import:R0603")
      (libsource (lib "eagle-import") (part "R-US_R0603"))
    )
    (comp (ref "R24")
      (value "510")
      (footprint "eagle-import:R0603")
      (libsource (lib "eagle-import") (part "R-US_R0603"))
    )
    (comp (ref "R25")
      (value "510")
      (footprint "eagle-import:R0603")
      (libsource (lib "eagle-import") (part "R-US_R0603"))
    )
    (comp (ref "R26")
      (value "120k")
      (footprint "eagle-import:R0603")
      (libsource (lib "eagle-import") (part "R-US_R0603"))
    )
    (comp (ref "R27")
      (value "120k")
      (footprint "eagle-import:R0603")
      (libsource (lib "eagle-import") (part "R-US_R0603"))
    )
    (comp (ref "R28")
      (value "200k")
      (footprint "eagle-import:R0603")
      (libsource (lib "eagle-import") (part "R-US_R0603"))
    )
    (comp (ref "R29")
      (value "200k")
      (footprint "eagle-import:R0603")
      (libsource (lib "eagle-import") (part "R-US_R0603"))
    )
    (comp (ref "R30")
      (value "120k")
      (footprint "eagle-import:R0603")
      (libsource (lib "eagle-import") (part "R-US_R0603"))
    )
    (comp (ref "R31")
      (value "120k")
      (footprint "eagle-import:R0603")
      (libsource (lib "eagle-import") (part "R-US_R0603"))
    )
    (comp (ref "R32")
      (value "100k")
      (footprint "eagle-import:R0603")
      (libsource (lib "eagle-import") (part "R-US_R0603"))
    )
    (comp (ref "R33")
      (value "100k")
      (footprint "eagle-import:R0603")
      (libsource (lib "eagle-import") (part "R-US_R0603"))
    )
    (comp (ref "R100")
      (value "10kB")
      (footprint "eagle-import:ALPS_POT_VERTICAL_PS")
      (libsource (lib "eagle-import") (part "POT_USVERTICAL_PS"))
    )
    (comp (ref "R101")
      (value "10kB")
      (footprint "eagle-import:ALPS_POT_VERTICAL_PS")
      (libsource (lib "eagle-import") (part "POT_USVERTICAL_PS"))
    )
    (comp (ref "R108")
      (value "100k")
      (footprint "eagle-import:R0603")
      (libsource (lib "eagle-import") (part "R-US_R0603"))
    )
    (comp (ref "R109")
      (value "100k")
      (footprint "eagle-import:R0603")
      (libsource (lib "eagle-import") (part "R-US_R0603"))
    )
    (comp (ref "C21")
      (value "100n")
      (footprint "eagle-import:C0603")
      (libsource (lib "eagle-import") (part "C-USC0603"))
    )
    (comp (ref "C22")
      (value "100n")
      (footprint "eagle-import:C0603")
      (libsource (lib "eagle-import") (part "C-USC0603"))
    )
    (comp (ref "C23")
      (value "560p")
      (footprint "eagle-import:C0603")
      (libsource (lib "eagle-import") (part "C-USC0603"))
    )
    (comp (ref "C24")
      (value "560p")
      (footprint "eagle-import:C0603")
      (libsource (lib "eagle-import") (part "C-USC0603"))
    )
    (comp (ref "C25")
      (value "68p")
      (footprint "eagle-import:C0603")
      (libsource (lib "eagle-import") (part "C-USC0603"))
    )
    (comp (ref "C26")
      (value "68p")
      (footprint "eagle-import:C0603")
      (libsource (lib "eagle-import") (part "C-USC0603"))
    )
    (comp (ref "C27")
      (value "100n")
      (footprint "eagle-import:C0603")
      (libsource (lib "eagle-import") (part "C-USC0603"))
    )
    (comp (ref "C28")
      (value "100n")
      (footprint "eagle-import:C0603")
      (libsource (lib "eagle-import") (part "C-USC0603"))
    )
    (comp (ref "C29")
      (value "560p")
      (footprint "eagle-import:C0603")
      (libsource (lib "eagle-import") (part "C-USC0603"))
    )
    (comp (ref "C30")
      (value "560p")
      (footprint "eagle-import:C0603")
      (libsource (lib "eagle-import") (part "C-USC0603"))
    )
    (comp (ref "C31")
      (value "100n")
      (footprint "eagle-import:C0603")
      (libsource (lib "eagle-import") (part "C-USC0603"))
    )
    (comp (ref "C32")
      (value "560p")
      (footprint "eagle-import:C0603")
      (libsource (lib "eagle-import") (part "C-USC0603"))
    )
    (comp (ref "C33")
      (value "560p")
      (footprint "eagle-import:C0603")
      (libsource (lib "eagle-import") (part "C-USC0603"))
    )
    (comp (ref "C34")
      (value "560p")
      (footprint "eagle-import:C0603")
      (libsource (lib "eagle-import") (part "C-USC0603"))
    )
    (comp (ref "C35")
      (value "100n")
      (footprint "eagle-import:C0603")
      (libsource (lib "eagle-import") (part "C-USC0603"))
    )
    (comp (ref "D7")
      (value "1N4148")
      (footprint "eagle-import:SOD323-W")
      (libsource (lib "eagle-import") (part "DIODE-SOD323-W"))
    )
    (comp (ref "D8")
      (value "1N4148")
      (footprint "eagle-import:SOD323-W")
      (libsource (lib "eagle-import") (part "DIODE-SOD323-W"))
    )
    (comp (ref "D9")
      (value "1N4148")
      (footprint "eagle-import:SOD323-W")
      (libsource (lib "eagle-import") (part "DIODE-SOD323-W"))
    )
    (comp (ref "D15")
      (value "1N4148")
      (footprint "eagle-import:SOD323-W")
      (libsource (lib "eagle-import") (part "DIODE-SOD323-W"))
    )
    (comp (ref "D18")
      (value "1N4148")
      (footprint "eagle-import:SOD323-W")
      (libsource (lib "eagle-import") (part "DIODE-SOD323-W"))
    )
    (comp (ref "IC6")
      (value "TL074D")
      (footprint "eagle-import:SO14")
      (libsource (lib "eagle-import") (part "TL074D"))
    )
    (comp (ref "IC7")
      (value "TL074D")
      (footprint "eagle-import:SO14")
      (libsource (lib "eagle-import") (part "TL074D"))
    )
    (comp (ref "IC8")
      (value "V2164SZ")
      (footprint "eagle-import:SOIC16N")
      (libsource (lib "eagle-import") (part "SSM2164S"))
    )
    (comp (ref "J3")
      (value "PJ301_THONKICONN6")
      (footprint "eagle-import:WQP_PJ_301M6")
      (libsource (lib "eagle-import") (part "PJ301_THONKICONN6"))
    )
    (comp (ref "J4")
      (value "PJ301_THONKICONN6")
      (footprint "eagle-import:WQP_PJ_301M6")
      (libsource (lib "eagle-import") (part "PJ301_THONKICONN6"))
    )
    (comp (ref "J5")
      (value "PJ301_THONKICONN6")
      (footprint "eagle-import:WQP_PJ_301M6")
      (libsource (lib "eagle-import") (part "PJ301_THONKICONN6"))
    )
    (comp (ref "J15")
      (value "PJ301_THONKICONN6")
      (footprint "eagle-import:WQP_PJ_301M6")
      (libsource (lib "eagle-import") (part "PJ301_THONKICONN6"))
    )
    (comp (ref "J16")
      (value "PJ301_THONKICONN6")
      (footprint "eagle-import:WQP_PJ_301M6")
      (libsource (lib "eagle-import") (part "PJ301_THONKICONN6"))
    )
    (comp (ref "J17")
      (value "PJ301_THONKICONN6")
      (footprint "eagle-import:WQP_PJ_301M6")
      (libsource (lib "eagle-import") (part "PJ301_THONKICONN6"))
    )
    (comp (ref "R34")
      (value "10kB")
      (footprint "eagle-import:ALPS_POT_VERTICAL_PS")
      (libsource (lib "eagle-import") (part "POT_USVERTICAL_PS"))
    )
    (comp (ref "R35")
      (value "100k")
      (footprint "eagle-import:R0603")
      (libsource (lib "eagle-import") (part "R-US_R0603"))
    )
    (comp (ref "R36")
      (value "10kB")
      (footprint "eagle-import:ALPS_POT_VERTICAL_PS")
      (libsource (lib "eagle-import") (part "POT_USVERTICAL_PS"))
    )
    (comp (ref "R37")
      (value "100k")
      (footprint "eagle-import:R0603")
      (libsource (lib "eagle-import") (part "R-US_R0603"))
    )
    (comp (ref "R38")
      (value "100k")
      (footprint "eagle-import:R0603")
      (libsource (lib "eagle-import") (part "R-US_R0603"))
    )
    (comp (ref "R39")
      (value "100k")
      (footprint "eagle-import:R0603")
      (libsource (lib "eagle-import") (part "R-US_R0603"))
    )
    (comp (ref "R40")
      (value "100k")
      (footprint "eagle-import:R0603")
      (libsource (lib "eagle-import") (part "R-US_R0603"))
    )
    (comp (ref "R41")
      (value "100k")
      (footprint "eagle-import:R0603")
      (libsource (lib "eagle-import") (part "R-US_R0603"))
    )
    (comp (ref "R42")
      (value "10kB")
      (footprint "eagle-import:ALPS_POT_VERTICAL")
      (libsource (lib "eagle-import") (part "POT_USVERTICAL"))
    )
    (comp (ref "R43")
      (value "100k")
      (footprint "eagle-import:R0603")
      (libsource (lib "eagle-import") (part "R-US_R0603"))
    )
    (comp (ref "R44")
      (value "120k")
      (footprint "eagle-import:R0603")
      (libsource (lib "eagle-import") (part "R-US_R0603"))
    )
    (comp (ref "R45")
      (value "120k")
      (footprint "eagle-import:R0603")
      (libsource (lib "eagle-import") (part "R-US_R0603"))
    )
    (comp (ref "R46")
      (value "200k")
      (footprint "eagle-import:R0603")
      (libsource (lib "eagle-import") (part "R-US_R0603"))
    )
    (comp (ref "R47")
      (value "100k")
      (footprint "eagle-import:R0603")
      (libsource (lib "eagle-import") (part "R-US_R0603"))
    )
    (comp (ref "R48")
      (value "100k")
      (footprint "eagle-import:R0603")
      (libsource (lib "eagle-import") (part "R-US_R0603"))
    )
    (comp (ref "R49")
      (value "100k")
      (footprint "eagle-import:R0603")
      (libsource (lib "eagle-import") (part "R-US_R0603"))
    )
    (comp (ref "R50")
      (value "12k")
      (footprint "eagle-import:R0603")
      (libsource (lib "eagle-import") (part "R-US_R0603"))
    )
    (comp (ref "R51")
      (value "18k")
      (footprint "eagle-import:R0603")
      (libsource (lib "eagle-import") (part "R-US_R0603"))
    )
    (comp (ref "R52")
      (value "100k")
      (footprint "eagle-import:R0603")
      (libsource (lib "eagle-import") (part "R-US_R0603"))
    )
    (comp (ref "R53")
      (value "100k")
      (footprint "eagle-import:R0603")
      (libsource (lib "eagle-import") (part "R-US_R0603"))
    )
    (comp (ref "R54")
      (value "150k")
      (footprint "eagle-import:R0603")
      (libsource (lib "eagle-import") (part "R-US_R0603"))
    )
    (comp (ref "R55")
      (value "100k")
      (footprint "eagle-import:R0603")
      (libsource (lib "eagle-import") (part "R-US_R0603"))
    )
    (comp (ref "R56")
      (value "510")
      (footprint "eagle-import:R0603")
      (libsource (lib "eagle-import") (part "R-US_R0603"))
    )
    (comp (ref "R57")
      (value "510")
      (footprint "eagle-import:R0603")
      (libsource (lib "eagle-import") (part "R-US_R0603"))
    )
    (comp (ref "R58")
      (value "100k")
      (footprint "eagle-import:R0603")
      (libsource (lib "eagle-import") (part "R-US_R0603"))
    )
    (comp (ref "R59")
      (value "100k")
      (footprint "eagle-import:R0603")
      (libsource (lib "eagle-import") (part "R-US_R0603"))
    )
    (comp (ref "R60")
      (value "22k")
      (footprint "eagle-import:R0603")
      (libsource (lib "eagle-import") (part "R-US_R0603"))
    )
    (comp (ref "R61")
      (value "510")
      (footprint "eagle-import:R0603")
      (libsource (lib "eagle-import") (part "R-US_R0603"))
    )
    (comp (ref "R62")
      (value "150k")
      (footprint "eagle-import:R0603")
      (libsource (lib "eagle-import") (part "R-US_R0603"))
    )
    (comp (ref "R64")
      (value "510")
      (footprint "eagle-import:R0603")
      (libsource (lib "eagle-import") (part "R-US_R0603"))
    )
    (comp (ref "R66")
      (value "100k")
      (footprint "eagle-import:R0603")
      (libsource (lib "eagle-import") (part "R-US_R0603"))
    )
    (comp (ref "R67")
      (value "100k")
      (footprint "eagle-import:R0603")
      (libsource (lib "eagle-import") (part "R-US_R0603"))
    )
    (comp (ref "R123")
      (value "1.0k")
      (footprint "eagle-import:R0603")
      (libsource (lib "eagle-import") (part "R-US_R0603"))
    )
    (comp (ref "R124")
      (value "1.0k")
      (footprint "eagle-import:R0603")
      (libsource (lib "eagle-import") (part "R-US_R0603"))
    )
    (comp (ref "R125")
      (value "1.0k")
      (footprint "eagle-import:R0603")
      (libsource (lib "eagle-import") (part "R-US_R0603"))
    )
  )
  (nets
    (net (code "1") (name "AREF_+10") (class "Default")
      (node (ref "C3") (pin "1") (pinfunction "1_1") (pintype "passive"))
      (node (ref "IC1") (pin "1") (pinfunction "C_1") (pintype "passive"))
      (node (ref "R1") (pin "2") (pinfunction "2_2") (pintype "passive"))
      (node (ref "R118") (pin "2") (pinfunction "2_2") (pintype "passive"))
      (node (ref "R121") (pin "2") (pinfunction "2_2") (pintype "passive"))
      (node (ref "R28") (pin "1") (pinfunction "1_1") (pintype "passive"))
      (node (ref "R29") (pin "1") (pinfunction "1_1") (pintype "passive"))
      (node (ref "R46") (pin "1") (pinfunction "1_1") (pintype "passive"))
      (node (ref "R80") (pin "1") (pinfunction "1_1") (pintype "passive"))
    )
    (net (code "2") (name "AREF_-10") (class "Default")
      (node (ref "C4") (pin "1") (pinfunction "1_1") (pintype "passive"))
      (node (ref "IC2") (pin "2") (pinfunction "A_2") (pintype "passive"))
      (node (ref "R108") (pin "1") (pinfunction "1_1") (pintype "passive"))
      (node (ref "R109") (pin "1") (pinfunction "1_1") (pintype "passive"))
      (node (ref "R12") (pin "1") (pinfunction "1_1") (pintype "passive"))
      (node (ref "R2") (pin "2") (pinfunction "2_2") (pintype "passive"))
      (node (ref "R43") (pin "1") (pinfunction "1_1") (pintype "passive"))
      (node (ref "R49") (pin "1") (pinfunction "1_1") (pintype "passive"))
      (node (ref "R5") (pin "1") (pinfunction "1_1") (pintype "passive"))
      (node (ref "R54") (pin "1") (pinfunction "1_1") (pintype "passive"))
      (node (ref "R70") (pin "1") (pinfunction "1_1") (pintype "passive"))
      (node (ref "R77") (pin "1") (pinfunction "1_1") (pintype "passive"))
      (node (ref "R83") (pin "1") (pinfunction "1_1") (pintype "passive"))
    )
    (net (code "3") (name "BP_1") (class "Default")
      (node (ref "C40") (pin "2") (pinfunction "2_2") (pintype "passive"))
      (node (ref "IC9") (pin "7") (pinfunction "OUT_7") (pintype "output"))
      (node (ref "R127") (pin "1") (pinfunction "1_1") (pintype "passive"))
      (node (ref "R87") (pin "1") (pinfunction "1_1") (pintype "passive"))
      (node (ref "R98") (pin "1") (pinfunction "1_1") (pintype "passive"))
    )
    (net (code "4") (name "BP_2") (class "Default")
      (node (ref "C25") (pin "2") (pinfunction "2_2") (pintype "passive"))
      (node (ref "IC6") (pin "7") (pinfunction "OUT_7") (pintype "output"))
      (node (ref "R124") (pin "1") (pinfunction "1_1") (pintype "passive"))
      (node (ref "R53") (pin "1") (pinfunction "1_1") (pintype "passive"))
      (node (ref "R66") (pin "1") (pinfunction "1_1") (pintype "passive"))
    )
    (net (code "5") (name "F_GLOBAL") (class "Default")
      (node (ref "J11") (pin "P3") (pinfunction "3_P3") (pintype "passive"))
      (node (ref "R47") (pin "1") (pinfunction "1_1") (pintype "passive"))
      (node (ref "R7") (pin "1") (pinfunction "1_1") (pintype "passive"))
      (node (ref "R8") (pin "1") (pinfunction "1_1") (pintype "passive"))
      (node (ref "R81") (pin "1") (pinfunction "1_1") (pintype "passive"))
    )
    (net (code "6") (name "GAIN_GLOBAL") (class "Default")
      (node (ref "J12") (pin "P3") (pinfunction "3_P3") (pintype "passive"))
      (node (ref "R26") (pin "1") (pinfunction "1_1") (pintype "passive"))
      (node (ref "R31") (pin "1") (pinfunction "1_1") (pintype "passive"))
      (node (ref "R44") (pin "1") (pinfunction "1_1") (pintype "passive"))
      (node (ref "R79") (pin "1") (pinfunction "1_1") (pintype "passive"))
    )
    (net (code "7") (name "GND") (class "Default")
      (node (ref "C1") (pin "-") (pinfunction "-_-") (pintype "passive"))
      (node (ref "C12") (pin "2") (pinfunction "2_2") (pintype "passive"))
      (node (ref "C13") (pin "1") (pinfunction "1_1") (pintype "passive"))
      (node (ref "C14") (pin "2") (pinfunction "2_2") (pintype "passive"))
      (node (ref "C15") (pin "2") (pinfunction "2_2") (pintype "passive"))
      (node (ref "C18") (pin "2") (pinfunction "2_2") (pintype "passive"))
      (node (ref "C19") (pin "2") (pinfunction "2_2") (pintype "passive"))
      (node (ref "C2") (pin "+") (pinfunction "+_+") (pintype "passive"))
      (node (ref "C20") (pin "1") (pinfunction "1_1") (pintype "passive"))
      (node (ref "C21") (pin "2") (pinfunction "2_2") (pintype "passive"))
      (node (ref "C22") (pin "1") (pinfunction "1_1") (pintype "passive"))
      (node (ref "C27") (pin "2") (pinfunction "2_2") (pintype "passive"))
      (node (ref "C28") (pin "1") (pinfunction "1_1") (pintype "passive"))
      (node (ref "C29") (pin "2") (pinfunction "2_2") (pintype "passive"))
      (node (ref "C3") (pin "2") (pinfunction "2_2") (pintype "passive"))
      (node (ref "C30") (pin "2") (pinfunction "2_2") (pintype "passive"))
      (node (ref "C31") (pin "2") (pinfunction "2_2") (pintype "passive"))
      (node (ref "C33") (pin "2") (pinfunction "2_2") (pintype "passive"))
      (node (ref "C34") (pin "2") (pinfunction "2_2") (pintype "passive"))
      (node (ref "C35") (pin "1") (pinfunction "1_1") (pintype "passive"))
      (node (ref "C36") (pin "2") (pinfunction "2_2") (pintype "passive"))
      (node (ref "C37") (pin "1") (pinfunction "1_1") (pintype "passive"))
      (node (ref "C4") (pin "2") (pinfunction "2_2") (pintype "passive"))
      (node (ref "C42") (pin "2") (pinfunction "2_2") (pintype "passive"))
      (node (ref "C43") (pin "2") (pinfunction "2_2") (pintype "passive"))
      (node (ref "C44") (pin "1") (pinfunction "1_1") (pintype "passive"))
      (node (ref "C45") (pin "2") (pinfunction "2_2") (pintype "passive"))
      (node (ref "C47") (pin "2") (pinfunction "2_2") (pintype "passive"))
      (node (ref "C48") (pin "2") (pinfunction "2_2") (pintype "passive"))
      (node (ref "C49") (pin "2") (pinfunction "2_2") (pintype "passive"))
      (node (ref "C5") (pin "2") (pinfunction "2_2") (pintype "passive"))
      (node (ref "C50") (pin "2") (pinfunction "2_2") (pintype "passive"))
      (node (ref "C51") (pin "1") (pinfunction "1_1") (pintype "passive"))
      (node (ref "C52") (pin "2") (pinfunction "2_2") (pintype "passive"))
      (node (ref "C53") (pin "1") (pinfunction "1_1") (pintype "passive"))
      (node (ref "C54") (pin "1") (pinfunction "1_1") (pintype "passive"))
      (node (ref "C55") (pin "2") (pinfunction "2_2") (pintype "passive"))
      (node (ref "C56") (pin "2") (pinfunction "2_2") (pintype "passive"))
      (node (ref "C58") (pin "-") (pinfunction "-_-") (pintype "passive"))
      (node (ref "C8") (pin "1") (pinfunction "1_1") (pintype "passive"))
      (node (ref "C9") (pin "2") (pinfunction "2_2") (pintype "passive"))
      (node (ref "D1") (pin "C") (pinfunction "C_C") (pintype "passive"))
      (node (ref "D10") (pin "A") (pinfunction "A_A") (pintype "passive"))
      (node (ref "D3") (pin "A") (pinfunction "A_A") (pintype "passive"))
      (node (ref "D4") (pin "A") (pinfunction "A_A") (pintype "passive"))
      (node (ref "D5") (pin "A") (pinfunction "A_A") (pintype "passive"))
      (node (ref "D6") (pin "A") (pinfunction "A_A") (pintype "passive"))
      (node (ref "D7") (pin "A") (pinfunction "A_A") (pintype "passive"))
      (node (ref "IC1") (pin "2") (pinfunction "A_2") (pintype "passive"))
      (node (ref "IC10") (pin "10") (pinfunction "+IN_10") (pintype "input"))
      (node (ref "IC10") (pin "12") (pinfunction "+IN_12") (pintype "input"))
      (node (ref "IC10") (pin "3") (pinfunction "+IN_3") (pintype "input"))
      (node (ref "IC10") (pin "5") (pinfunction "+IN_5") (pintype "input"))
      (node (ref "IC11") (pin "8") (pinfunction "GND_8") (pintype "power_in"))
      (node (ref "IC12") (pin "3") (pinfunction "+IN_3") (pintype "input"))
      (node (ref "IC12") (pin "5") (pinfunction "+IN_5") (pintype "input"))
      (node (ref "IC13") (pin "3") (pinfunction "+IN_3") (pintype "input"))
      (node (ref "IC13") (pin "5") (pinfunction "+IN_5") (pintype "input"))
      (node (ref "IC14") (pin "4") (pinfunction "V-_4") (pintype "power_in"))
      (node (ref "IC2") (pin "1") (pinfunction "C_1") (pintype "passive"))
      (node (ref "IC3") (pin "3") (pinfunction "+IN_3") (pintype "input"))
      (node (ref "IC3") (pin "5") (pinfunction "+IN_5") (pintype "input"))
      (node (ref "IC4") (pin "10") (pinfunction "+IN_10") (pintype "input"))
      (node (ref "IC4") (pin "12") (pinfunction "+IN_12") (pintype "input"))
      (node (ref "IC4") (pin "3") (pinfunction "+IN_3") (pintype "input"))
      (node (ref "IC4") (pin "5") (pinfunction "+IN_5") (pintype "input"))
      (node (ref "IC5") (pin "8") (pinfunction "GND_8") (pintype "power_in"))
      (node (ref "IC6") (pin "10") (pinfunction "+IN_10") (pintype "input"))
      (node (ref "IC6") (pin "12") (pinfunction "+IN_12") (pintype "input"))
      (node (ref "IC6") (pin "3") (pinfunction "+IN_3") (pintype "input"))
      (node (ref "IC6") (pin "5") (pinfunction "+IN_5") (pintype "input"))
      (node (ref "IC7") (pin "10") (pinfunction "+IN_10") (pintype "input"))
      (node (ref "IC7") (pin "12") (pinfunction "+IN_12") (pintype "input"))
      (node (ref "IC7") (pin "3") (pinfunction "+IN_3") (pintype "input"))
      (node (ref "IC7") (pin "5") (pinfunction "+IN_5") (pintype "input"))
      (node (ref "IC8") (pin "8") (pinfunction "GND_8") (pintype "power_in"))
      (node (ref "IC9") (pin "10") (pinfunction "+IN_10") (pintype "input"))
      (node (ref "IC9") (pin "12") (pinfunction "+IN_12") (pintype "input"))
      (node (ref "IC9") (pin "3") (pinfunction "+IN_3") (pintype "input"))
      (node (ref "IC9") (pin "5") (pinfunction "+IN_5") (pintype "input"))
      (node (ref "J1") (pin "P1") (pinfunction "1_P1") (pintype "passive"))
      (node (ref "J10") (pin "P1") (pinfunction "1_P1") (pintype "passive"))
      (node (ref "J11") (pin "P1") (pinfunction "1_P1") (pintype "passive"))
      (node (ref "J12") (pin "P1") (pinfunction "1_P1") (pintype "passive"))
      (node (ref "J13") (pin "P1") (pinfunction "1_P1") (pintype "passive"))
      (node (ref "J14") (pin "P1") (pinfunction "1_P1") (pintype "passive"))
      (node (ref "J15") (pin "P1") (pinfunction "1_P1") (pintype "passive"))
      (node (ref "J16") (pin "P1") (pinfunction "1_P1") (pintype "passive"))
      (node (ref "J17") (pin "P1") (pinfunction "1_P1") (pintype "passive"))
      (node (ref "J18") (pin "P1") (pinfunction "1_P1") (pintype "passive"))
      (node (ref "J19") (pin "P1") (pinfunction "1_P1") (pintype "passive"))
      (node (ref "J2") (pin "P1") (pinfunction "1_P1") (pintype "passive"))
      (node (ref "J20") (pin "P1") (pinfunction "1_P1") (pintype "passive"))
      (node (ref "J3") (pin "P1") (pinfunction "1_P1") (pintype "passive"))
      (node (ref "J4") (pin "P1") (pinfunction "1_P1") (pintype "passive"))
      (node (ref "J5") (pin "P1") (pinfunction "1_P1") (pintype "passive"))
      (node (ref "J6") (pin "P1") (pinfunction "1_P1") (pintype "passive"))
      (node (ref "J7") (pin "P1") (pinfunction "1_P1") (pintype "passive"))
      (node (ref "J8") (pin "P1") (pinfunction "1_P1") (pintype "passive"))
      (node (ref "J9") (pin "P1") (pinfunction "1_P1") (pintype "passive"))
      (node (ref "JP11") (pin "3") (pinfunction "3_3") (pintype "passive"))
      (node (ref "JP11") (pin "4") (pinfunction "4_4") (pintype "passive"))
      (node (ref "JP11") (pin "5") (pinfunction "5_5") (pintype "passive"))
      (node (ref "JP11") (pin "6") (pinfunction "6_6") (pintype "passive"))
      (node (ref "JP11") (pin "7") (pinfunction "7_7") (pintype "passive"))
      (node (ref "JP11") (pin "8") (pinfunction "8_8") (pintype "passive"))
      (node (ref "Q1") (pin "E") (pinfunction "E_E") (pintype "passive"))
      (node (ref "R100") (pin "P$1") (pinfunction "E_P$1") (pintype "passive"))
      (node (ref "R101") (pin "P$1") (pinfunction "E_P$1") (pintype "passive"))
      (node (ref "R116") (pin "1") (pinfunction "1_1") (pintype "passive"))
      (node (ref "R117") (pin "1") (pinfunction "1_1") (pintype "passive"))
      (node (ref "R120") (pin "1") (pinfunction "1_1") (pintype "passive"))
      (node (ref "R3") (pin "P$1") (pinfunction "E_P$1") (pintype "passive"))
      (node (ref "R34") (pin "P$1") (pinfunction "E_P$1") (pintype "passive"))
      (node (ref "R36") (pin "P$1") (pinfunction "E_P$1") (pintype "passive"))
      (node (ref "R4") (pin "P$1") (pinfunction "E_P$1") (pintype "passive"))
      (node (ref "R42") (pin "P$3") (pinfunction "A_P$3") (pintype "passive"))
      (node (ref "R65") (pin "P$3") (pinfunction "A_P$3") (pintype "passive"))
      (node (ref "R68") (pin "P$1") (pinfunction "E_P$1") (pintype "passive"))
      (node (ref "R69") (pin "P$1") (pinfunction "E_P$1") (pintype "passive"))
    )
    (net (code "8") (name "HP_1") (class "Default")
      (node (ref "IC9") (pin "1") (pinfunction "OUT_1") (pintype "output"))
      (node (ref "R126") (pin "1") (pinfunction "1_1") (pintype "passive"))
      (node (ref "R75") (pin "2") (pinfunction "2_2") (pintype "passive"))
      (node (ref "R86") (pin "1") (pinfunction "1_1") (pintype "passive"))
    )
    (net (code "9") (name "HP_2") (class "Default")
      (node (ref "IC6") (pin "1") (pinfunction "OUT_1") (pintype "output"))
      (node (ref "R123") (pin "1") (pinfunction "1_1") (pintype "passive"))
      (node (ref "R40") (pin "2") (pinfunction "2_2") (pintype "passive"))
      (node (ref "R52") (pin "1") (pinfunction "1_1") (pintype "passive"))
    )
    (net (code "10") (name "IN") (class "Default")
      (node (ref "IC12") (pin "7") (pinfunction "OUT_7") (pintype "output"))
      (node (ref "JP5") (pin "3") (pinfunction "3_3") (pintype "passive"))
      (node (ref "R103") (pin "2") (pinfunction "2_2") (pintype "passive"))
      (node (ref "R15") (pin "1") (pinfunction "1_1") (pintype "passive"))
      (node (ref "R16") (pin "1") (pinfunction "1_1") (pintype "passive"))
      (node (ref "R17") (pin "1") (pinfunction "1_1") (pintype "passive"))
      (node (ref "R37") (pin "1") (pinfunction "1_1") (pintype "passive"))
      (node (ref "R72") (pin "1") (pinfunction "1_1") (pintype "passive"))
    )
    (net (code "11") (name "MINUS_BUS") (class "Default")
      (node (ref "IC11") (pin "12") (pinfunction "OUT_12") (pintype "output"))
      (node (ref "IC13") (pin "2") (pinfunction "-IN_2") (pintype "input"))
      (node (ref "IC5") (pin "5") (pinfunction "OUT_5") (pintype "output"))
      (node (ref "IC8") (pin "12") (pinfunction "OUT_12") (pintype "output"))
      (node (ref "R104") (pin "2") (pinfunction "2_2") (pintype "passive"))
      (node (ref "R107") (pin "1") (pinfunction "1_1") (pintype "passive"))
      (node (ref "R19") (pin "2") (pinfunction "2_2") (pintype "passive"))
    )
    (net (code "12") (name "Net-(C14-Pad1)") (class "Default")
      (node (ref "C14") (pin "1") (pinfunction "1_1") (pintype "passive"))
      (node (ref "R21") (pin "1") (pinfunction "1_1") (pintype "passive"))
    )
    (net (code "13") (name "Net-(C15-Pad1)") (class "Default")
      (node (ref "C15") (pin "1") (pinfunction "1_1") (pintype "passive"))
      (node (ref "R20") (pin "1") (pinfunction "1_1") (pintype "passive"))
    )
    (net (code "14") (name "Net-(C18-Pad1)") (class "Default")
      (node (ref "C18") (pin "1") (pinfunction "1_1") (pintype "passive"))
      (node (ref "R24") (pin "1") (pinfunction "1_1") (pintype "passive"))
    )
    (net (code "15") (name "Net-(C19-Pad1)") (class "Default")
      (node (ref "C19") (pin "1") (pinfunction "1_1") (pintype "passive"))
      (node (ref "R25") (pin "1") (pinfunction "1_1") (pintype "passive"))
    )
    (net (code "16") (name "Net-(C29-Pad1)") (class "Default")
      (node (ref "C29") (pin "1") (pinfunction "1_1") (pintype "passive"))
      (node (ref "R56") (pin "1") (pinfunction "1_1") (pintype "passive"))
    )
    (net (code "17") (name "Net-(C30-Pad1)") (class "Default")
      (node (ref "C30") (pin "1") (pinfunction "1_1") (pintype "passive"))
      (node (ref "R57") (pin "1") (pinfunction "1_1") (pintype "passive"))
    )
    (net (code "18") (name "Net-(C33-Pad1)") (class "Default")
      (node (ref "C33") (pin "1") (pinfunction "1_1") (pintype "passive"))
      (node (ref "R61") (pin "1") (pinfunction "1_1") (pintype "passive"))
    )
    (net (code "19") (name "Net-(C34-Pad1)") (class "Default")
      (node (ref "C34") (pin "1") (pinfunction "1_1") (pintype "passive"))
      (node (ref "R64") (pin "1") (pinfunction "1_1") (pintype "passive"))
    )
    (net (code "20") (name "Net-(C45-Pad1)") (class "Default")
      (node (ref "C45") (pin "1") (pinfunction "1_1") (pintype "passive"))
      (node (ref "R89") (pin "1") (pinfunction "1_1") (pintype "passive"))
    )
    (net (code "21") (name "Net-(C47-Pad1)") (class "Default")
      (node (ref "C47") (pin "1") (pinfunction "1_1") (pintype "passive"))
      (node (ref "R90") (pin "1") (pinfunction "1_1") (pintype "passive"))
    )
    (net (code "22") (name "Net-(C48-Pad1)") (class "Default")
      (node (ref "C48") (pin "1") (pinfunction "1_1") (pintype "passive"))
      (node (ref "R94") (pin "1") (pinfunction "1_1") (pintype "passive"))
    )
    (net (code "23") (name "Net-(C49-Pad1)") (class "Default")
      (node (ref "C49") (pin "1") (pinfunction "1_1") (pintype "passive"))
      (node (ref "R97") (pin "1") (pinfunction "1_1") (pintype "passive"))
    )
    (net (code "24") (name "Net-(C55-Pad1)") (class "Default")
      (node (ref "C55") (pin "1") (pinfunction "1_1") (pintype "passive"))
      (node (ref "R113") (pin "2") (pinfunction "2_2") (pintype "passive"))
      (node (ref "R114") (pin "1") (pinfunction "1_1") (pintype "passive"))
    )
    (net (code "25") (name "Net-(C57-Pad1)") (class "Default")
      (node (ref "C57") (pin "1") (pinfunction "1_1") (pintype "passive"))
      (node (ref "R115") (pin "1") (pinfunction "1_1") (pintype "passive"))
    )
    (net (code "26") (name "Net-(D2-PadA)") (class "Default")
      (node (ref "D2") (pin "A") (pinfunction "A_A") (pintype "passive"))
      (node (ref "JP11") (pin "1") (pinfunction "1_1") (pintype "passive"))
      (node (ref "JP11") (pin "2") (pinfunction "2_2") (pintype "passive"))
    )
    (net (code "27") (name "Net-(D13-PadC)") (class "Default")
      (node (ref "D13") (pin "C") (pinfunction "C_C") (pintype "passive"))
      (node (ref "D14") (pin "C") (pinfunction "C_C") (pintype "passive"))
      (node (ref "R113") (pin "1") (pinfunction "1_1") (pintype "passive"))
    )
    (net (code "28") (name "Net-(IC3A--IN)") (class "Default")
      (node (ref "C6") (pin "1") (pinfunction "1_1") (pintype "passive"))
      (node (ref "IC3") (pin "2") (pinfunction "-IN_2") (pintype "input"))
      (node (ref "IC5") (pin "4") (pinfunction "OUT_4") (pintype "output"))
    )
    (net (code "29") (name "Net-(IC3A-OUT)") (class "Default")
      (node (ref "C6") (pin "2") (pinfunction "2_2") (pintype "passive"))
      (node (ref "IC3") (pin "1") (pinfunction "OUT_1") (pintype "output"))
      (node (ref "R11") (pin "2") (pinfunction "2_2") (pintype "passive"))
      (node (ref "R32") (pin "1") (pinfunction "1_1") (pintype "passive"))
      (node (ref "R33") (pin "1") (pinfunction "1_1") (pintype "passive"))
    )
    (net (code "30") (name "Net-(IC3B--IN)") (class "Default")
      (node (ref "C7") (pin "1") (pinfunction "1_1") (pintype "passive"))
      (node (ref "IC3") (pin "6") (pinfunction "-IN_6") (pintype "input"))
      (node (ref "IC5") (pin "13") (pinfunction "OUT_13") (pintype "output"))
    )
    (net (code "31") (name "Net-(IC3B-OUT)") (class "Default")
      (node (ref "C7") (pin "2") (pinfunction "2_2") (pintype "passive"))
      (node (ref "IC3") (pin "7") (pinfunction "OUT_7") (pintype "output"))
      (node (ref "R10") (pin "2") (pinfunction "2_2") (pintype "passive"))
      (node (ref "R18") (pin "1") (pinfunction "1_1") (pintype "passive"))
      (node (ref "R19") (pin "1") (pinfunction "1_1") (pintype "passive"))
    )
    (net (code "32") (name "Net-(IC4A--IN)") (class "Default")
      (node (ref "C10") (pin "2") (pinfunction "2_2") (pintype "passive"))
      (node (ref "IC4") (pin "2") (pinfunction "-IN_2") (pintype "input"))
      (node (ref "R13") (pin "1") (pinfunction "1_1") (pintype "passive"))
      (node (ref "R3") (pin "P$3") (pinfunction "A_P$3") (pintype "passive"))
      (node (ref "R6") (pin "2") (pinfunction "2_2") (pintype "passive"))
      (node (ref "R7") (pin "2") (pinfunction "2_2") (pintype "passive"))
    )
    (net (code "33") (name "Net-(IC4A-OUT)") (class "Default")
      (node (ref "C10") (pin "1") (pinfunction "1_1") (pintype "passive"))
      (node (ref "D3") (pin "C") (pinfunction "C_C") (pintype "passive"))
      (node (ref "IC4") (pin "1") (pinfunction "OUT_1") (pintype "output"))
      (node (ref "IC5") (pin "14") (pinfunction "CTRL_14") (pintype "input"))
      (node (ref "R13") (pin "2") (pinfunction "2_2") (pintype "passive"))
    )
    (net (code "34") (name "Net-(IC4B--IN)") (class "Default")
      (node (ref "C16") (pin "2") (pinfunction "2_2") (pintype "passive"))
      (node (ref "IC4") (pin "6") (pinfunction "-IN_6") (pintype "input"))
      (node (ref "R101") (pin "P$3") (pinfunction "A_P$3") (pintype "passive"))
      (node (ref "R22") (pin "1") (pinfunction "1_1") (pintype "passive"))
      (node (ref "R26") (pin "2") (pinfunction "2_2") (pintype "passive"))
      (node (ref "R27") (pin "2") (pinfunction "2_2") (pintype "passive"))
      (node (ref "R28") (pin "2") (pinfunction "2_2") (pintype "passive"))
    )
    (net (code "35") (name "Net-(IC4B-OUT)") (class "Default")
      (node (ref "C16") (pin "1") (pinfunction "1_1") (pintype "passive"))
      (node (ref "D6") (pin "C") (pinfunction "C_C") (pintype "passive"))
      (node (ref "IC4") (pin "7") (pinfunction "OUT_7") (pintype "output"))
      (node (ref "IC5") (pin "6") (pinfunction "CTRL_6") (pintype "input"))
      (node (ref "R22") (pin "2") (pinfunction "2_2") (pintype "passive"))
    )
    (net (code "36") (name "Net-(IC4C--IN)") (class "Default")
      (node (ref "C17") (pin "2") (pinfunction "2_2") (pintype "passive"))
      (node (ref "IC4") (pin "9") (pinfunction "-IN_9") (pintype "input"))
      (node (ref "R23") (pin "1") (pinfunction "1_1") (pintype "passive"))
      (node (ref "R29") (pin "2") (pinfunction "2_2") (pintype "passive"))
      (node (ref "R30") (pin "2") (pinfunction "2_2") (pintype "passive"))
      (node (ref "R31") (pin "2") (pinfunction "2_2") (pintype "passive"))
      (node (ref "R4") (pin "P$3") (pinfunction "A_P$3") (pintype "passive"))
    )
    (net (code "37") (name "Net-(IC4C-OUT)") (class "Default")
      (node (ref "C17") (pin "1") (pinfunction "1_1") (pintype "passive"))
      (node (ref "D5") (pin "C") (pinfunction "C_C") (pintype "passive"))
      (node (ref "IC4") (pin "8") (pinfunction "OUT_8") (pintype "output"))
      (node (ref "IC5") (pin "11") (pinfunction "CTRL_11") (pintype "input"))
      (node (ref "R23") (pin "2") (pinfunction "2_2") (pintype "passive"))
    )
    (net (code "38") (name "Net-(IC4D--IN)") (class "Default")
      (node (ref "C11") (pin "2") (pinfunction "2_2") (pintype "passive"))
      (node (ref "IC4") (pin "13") (pinfunction "-IN_13") (pintype "input"))
      (node (ref "R100") (pin "P$3") (pinfunction "A_P$3") (pintype "passive"))
      (node (ref "R14") (pin "1") (pinfunction "1_1") (pintype "passive"))
      (node (ref "R8") (pin "2") (pinfunction "2_2") (pintype "passive"))
      (node (ref "R9") (pin "2") (pinfunction "2_2") (pintype "passive"))
    )
    (net (code "39") (name "Net-(IC4D-OUT)") (class "Default")
      (node (ref "C11") (pin "1") (pinfunction "1_1") (pintype "passive"))
      (node (ref "D4") (pin "C") (pinfunction "C_C") (pintype "passive"))
      (node (ref "IC4") (pin "14") (pinfunction "OUT_14") (pintype "output"))
      (node (ref "IC5") (pin "3") (pinfunction "CTRL_3") (pintype "input"))
      (node (ref "R14") (pin "2") (pinfunction "2_2") (pintype "passive"))
    )
    (net (code "40") (name "Net-(IC5A-IN)") (class "Default")
      (node (ref "IC5") (pin "2") (pinfunction "IN_2") (pintype "input"))
      (node (ref "R11") (pin "1") (pinfunction "1_1") (pintype "passive"))
      (node (ref "R15") (pin "2") (pinfunction "2_2") (pintype "passive"))
      (node (ref "R20") (pin "2") (pinfunction "2_2") (pintype "passive"))
    )
    (net (code "41") (name "Net-(IC5B-IN)") (class "Default")
      (node (ref "IC5") (pin "7") (pinfunction "IN_7") (pintype "input"))
      (node (ref "R25") (pin "2") (pinfunction "2_2") (pintype "passive"))
      (node (ref "R32") (pin "2") (pinfunction "2_2") (pintype "passive"))
    )
    (net (code "42") (name "Net-(IC5C-IN)") (class "Default")
      (node (ref "IC5") (pin "10") (pinfunction "IN_10") (pintype "input"))
      (node (ref "R17") (pin "2") (pinfunction "2_2") (pintype "passive"))
      (node (ref "R18") (pin "2") (pinfunction "2_2") (pintype "passive"))
      (node (ref "R24") (pin "2") (pinfunction "2_2") (pintype "passive"))
    )
    (net (code "43") (name "Net-(IC5D-IN)") (class "Default")
      (node (ref "IC5") (pin "15") (pinfunction "IN_15") (pintype "input"))
      (node (ref "R10") (pin "1") (pinfunction "1_1") (pintype "passive"))
      (node (ref "R16") (pin "2") (pinfunction "2_2") (pintype "passive"))
      (node (ref "R21") (pin "2") (pinfunction "2_2") (pintype "passive"))
    )
    (net (code "44") (name "Net-(IC6A--IN)") (class "Default")
      (node (ref "IC6") (pin "2") (pinfunction "-IN_2") (pintype "input"))
      (node (ref "R35") (pin "1") (pinfunction "1_1") (pintype "passive"))
      (node (ref "R37") (pin "2") (pinfunction "2_2") (pintype "passive"))
      (node (ref "R38") (pin "1") (pinfunction "1_1") (pintype "passive"))
      (node (ref "R40") (pin "1") (pinfunction "1_1") (pintype "passive"))
    )
    (net (code "45") (name "Net-(IC6B--IN)") (class "Default")
      (node (ref "C25") (pin "1") (pinfunction "1_1") (pintype "passive"))
      (node (ref "IC6") (pin "6") (pinfunction "-IN_6") (pintype "input"))
      (node (ref "IC8") (pin "4") (pinfunction "OUT_4") (pintype "output"))
    )
    (net (code "46") (name "Net-(IC6C--IN)") (class "Default")
      (node (ref "C26") (pin "1") (pinfunction "1_1") (pintype "passive"))
      (node (ref "IC6") (pin "9") (pinfunction "-IN_9") (pintype "input"))
      (node (ref "IC8") (pin "13") (pinfunction "OUT_13") (pintype "output"))
    )
    (net (code "47") (name "Net-(IC6C-OUT)") (class "Default")
      (node (ref "C26") (pin "2") (pinfunction "2_2") (pintype "passive"))
      (node (ref "IC6") (pin "8") (pinfunction "OUT_8") (pintype "output"))
      (node (ref "R125") (pin "1") (pinfunction "1_1") (pintype "passive"))
      (node (ref "R35") (pin "2") (pinfunction "2_2") (pintype "passive"))
    )
    (net (code "48") (name "Net-(IC6D--IN)") (class "Default")
      (node (ref "IC6") (pin "13") (pinfunction "-IN_13") (pintype "input"))
      (node (ref "IC8") (pin "5") (pinfunction "OUT_5") (pintype "output"))
      (node (ref "R41") (pin "2") (pinfunction "2_2") (pintype "passive"))
    )
    (net (code "49") (name "Net-(IC6D-OUT)") (class "Default")
      (node (ref "IC6") (pin "14") (pinfunction "OUT_14") (pintype "output"))
      (node (ref "R38") (pin "2") (pinfunction "2_2") (pintype "passive"))
      (node (ref "R39") (pin "1") (pinfunction "1_1") (pintype "passive"))
      (node (ref "R55") (pin "1") (pinfunction "1_1") (pintype "passive"))
      (node (ref "R67") (pin "1") (pinfunction "1_1") (pintype "passive"))
    )
    (net (code "50") (name "Net-(IC7A--IN)") (class "Default")
      (node (ref "C23") (pin "2") (pinfunction "2_2") (pintype "passive"))
      (node (ref "IC7") (pin "2") (pinfunction "-IN_2") (pintype "input"))
      (node (ref "R36") (pin "P$3") (pinfunction "A_P$3") (pintype "passive"))
      (node (ref "R44") (pin "2") (pinfunction "2_2") (pintype "passive"))
      (node (ref "R45") (pin "2") (pinfunction "2_2") (pintype "passive"))
      (node (ref "R46") (pin "2") (pinfunction "2_2") (pintype "passive"))
      (node (ref "R50") (pin "1") (pinfunction "1_1") (pintype "passive"))
    )
    (net (code "51") (name "Net-(IC7A-OUT)") (class "Default")
      (node (ref "C23") (pin "1") (pinfunction "1_1") (pintype "passive"))
      (node (ref "D7") (pin "C") (pinfunction "C_C") (pintype "passive"))
      (node (ref "IC7") (pin "1") (pinfunction "OUT_1") (pintype "output"))
      (node (ref "IC8") (pin "11") (pinfunction "CTRL_11") (pintype "input"))
      (node (ref "R50") (pin "2") (pinfunction "2_2") (pintype "passive"))
    )
    (net (code "52") (name "Net-(IC7B--IN)") (class "Default")
      (node (ref "IC7") (pin "6") (pinfunction "-IN_6") (pintype "input"))
      (node (ref "R58") (pin "2") (pinfunction "2_2") (pintype "passive"))
      (node (ref "R59") (pin "1") (pinfunction "1_1") (pintype "passive"))
    )
    (net (code "53") (name "Net-(IC7B-OUT)") (class "Default")
      (node (ref "IC7") (pin "7") (pinfunction "OUT_7") (pintype "output"))
      (node (ref "R59") (pin "2") (pinfunction "2_2") (pintype "passive"))
      (node (ref "R62") (pin "1") (pinfunction "1_1") (pintype "passive"))
    )
    (net (code "54") (name "Net-(IC7C--IN)") (class "Default")
      (node (ref "C32") (pin "2") (pinfunction "2_2") (pintype "passive"))
      (node (ref "D9") (pin "A") (pinfunction "A_A") (pintype "passive"))
      (node (ref "IC7") (pin "9") (pinfunction "-IN_9") (pintype "input"))
      (node (ref "R42") (pin "P$1") (pinfunction "E_P$1") (pintype "passive"))
      (node (ref "R60") (pin "1") (pinfunction "1_1") (pintype "passive"))
      (node (ref "R62") (pin "2") (pinfunction "2_2") (pintype "passive"))
    )
    (net (code "55") (name "Net-(IC7C-OUT)") (class "Default")
      (node (ref "D18") (pin "A") (pinfunction "A_A") (pintype "passive"))
      (node (ref "D9") (pin "C") (pinfunction "C_C") (pintype "passive"))
      (node (ref "IC7") (pin "8") (pinfunction "OUT_8") (pintype "output"))
    )
    (net (code "56") (name "Net-(IC7D--IN)") (class "Default")
      (node (ref "C24") (pin "2") (pinfunction "2_2") (pintype "passive"))
      (node (ref "D8") (pin "A") (pinfunction "A_A") (pintype "passive"))
      (node (ref "IC7") (pin "13") (pinfunction "-IN_13") (pintype "input"))
      (node (ref "R34") (pin "P$3") (pinfunction "A_P$3") (pintype "passive"))
      (node (ref "R47") (pin "2") (pinfunction "2_2") (pintype "passive"))
      (node (ref "R48") (pin "2") (pinfunction "2_2") (pintype "passive"))
      (node (ref "R51") (pin "1") (pinfunction "1_1") (pintype "passive"))
    )
    (net (code "57") (name "Net-(IC7D-OUT)") (class "Default")
      (node (ref "D15") (pin "A") (pinfunction "A_A") (pintype "passive"))
      (node (ref "D8") (pin "C") (pinfunction "C_C") (pintype "passive"))
      (node (ref "IC7") (pin "14") (pinfunction "OUT_14") (pintype "output"))
    )
    (net (code "58") (name "Net-(IC8A-CTRL)") (class "Default")
      (node (ref "C24") (pin "1") (pinfunction "1_1") (pintype "passive"))
      (node (ref "D15") (pin "C") (pinfunction "C_C") (pintype "passive"))
      (node (ref "IC8") (pin "14") (pinfunction "CTRL_14") (pintype "input"))
      (node (ref "IC8") (pin "3") (pinfunction "CTRL_3") (pintype "input"))
      (node (ref "R51") (pin "2") (pinfunction "2_2") (pintype "passive"))
    )
    (net (code "59") (name "Net-(IC8A-IN)") (class "Default")
      (node (ref "IC8") (pin "2") (pinfunction "IN_2") (pintype "input"))
      (node (ref "R52") (pin "2") (pinfunction "2_2") (pintype "passive"))
      (node (ref "R56") (pin "2") (pinfunction "2_2") (pintype "passive"))
    )
    (net (code "60") (name "Net-(IC8B-CTRL)") (class "Default")
      (node (ref "C32") (pin "1") (pinfunction "1_1") (pintype "passive"))
      (node (ref "D18") (pin "C") (pinfunction "C_C") (pintype "passive"))
      (node (ref "IC8") (pin "6") (pinfunction "CTRL_6") (pintype "input"))
      (node (ref "R60") (pin "2") (pinfunction "2_2") (pintype "passive"))
    )
    (net (code "61") (name "Net-(IC8B-IN)") (class "Default")
      (node (ref "IC8") (pin "7") (pinfunction "IN_7") (pintype "input"))
      (node (ref "R61") (pin "2") (pinfunction "2_2") (pintype "passive"))
      (node (ref "R66") (pin "2") (pinfunction "2_2") (pintype "passive"))
    )
    (net (code "62") (name "Net-(IC8C-IN)") (class "Default")
      (node (ref "IC8") (pin "10") (pinfunction "IN_10") (pintype "input"))
      (node (ref "R64") (pin "2") (pinfunction "2_2") (pintype "passive"))
      (node (ref "R67") (pin "2") (pinfunction "2_2") (pintype "passive"))
    )
    (net (code "63") (name "Net-(IC8D-IN)") (class "Default")
      (node (ref "IC8") (pin "15") (pinfunction "IN_15") (pintype "input"))
      (node (ref "R53") (pin "2") (pinfunction "2_2") (pintype "passive"))
      (node (ref "R57") (pin "2") (pinfunction "2_2") (pintype "passive"))
    )
    (net (code "64") (name "Net-(IC9A--IN)") (class "Default")
      (node (ref "IC9") (pin "2") (pinfunction "-IN_2") (pintype "input"))
      (node (ref "R71") (pin "1") (pinfunction "1_1") (pintype "passive"))
      (node (ref "R72") (pin "2") (pinfunction "2_2") (pintype "passive"))
      (node (ref "R73") (pin "1") (pinfunction "1_1") (pintype "passive"))
      (node (ref "R75") (pin "1") (pinfunction "1_1") (pintype "passive"))
    )
    (net (code "65") (name "Net-(IC9C-OUT)") (class "Default")
      (node (ref "C41") (pin "2") (pinfunction "2_2") (pintype "passive"))
      (node (ref "IC9") (pin "8") (pinfunction "OUT_8") (pintype "output"))
      (node (ref "R128") (pin "1") (pinfunction "1_1") (pintype "passive"))
      (node (ref "R71") (pin "2") (pinfunction "2_2") (pintype "passive"))
    )
    (net (code "66") (name "Net-(IC9D-OUT)") (class "Default")
      (node (ref "IC9") (pin "14") (pinfunction "OUT_14") (pintype "output"))
      (node (ref "R73") (pin "2") (pinfunction "2_2") (pintype "passive"))
      (node (ref "R74") (pin "1") (pinfunction "1_1") (pintype "passive"))
      (node (ref "R88") (pin "1") (pinfunction "1_1") (pintype "passive"))
      (node (ref "R99") (pin "1") (pinfunction "1_1") (pintype "passive"))
    )
    (net (code "67") (name "Net-(IC10A--IN)") (class "Default")
      (node (ref "C38") (pin "2") (pinfunction "2_2") (pintype "passive"))
      (node (ref "IC10") (pin "2") (pinfunction "-IN_2") (pintype "input"))
      (node (ref "R69") (pin "P$3") (pinfunction "A_P$3") (pintype "passive"))
      (node (ref "R78") (pin "2") (pinfunction "2_2") (pintype "passive"))
      (node (ref "R79") (pin "2") (pinfunction "2_2") (pintype "passive"))
      (node (ref "R80") (pin "2") (pinfunction "2_2") (pintype "passive"))
      (node (ref "R84") (pin "1") (pinfunction "1_1") (pintype "passive"))
    )
    (net (code "68") (name "Net-(IC10A-OUT)") (class "Default")
      (node (ref "C38") (pin "1") (pinfunction "1_1") (pintype "passive"))
      (node (ref "D10") (pin "C") (pinfunction "C_C") (pintype "passive"))
      (node (ref "IC10") (pin "1") (pinfunction "OUT_1") (pintype "output"))
      (node (ref "IC11") (pin "11") (pinfunction "CTRL_11") (pintype "input"))
      (node (ref "R84") (pin "2") (pinfunction "2_2") (pintype "passive"))
    )
    (net (code "69") (name "Net-(IC10B--IN)") (class "Default")
      (node (ref "IC10") (pin "6") (pinfunction "-IN_6") (pintype "input"))
      (node (ref "R91") (pin "2") (pinfunction "2_2") (pintype "passive"))
      (node (ref "R92") (pin "1") (pinfunction "1_1") (pintype "passive"))
    )
    (net (code "70") (name "Net-(IC10B-OUT)") (class "Default")
      (node (ref "IC10") (pin "7") (pinfunction "OUT_7") (pintype "output"))
      (node (ref "R92") (pin "2") (pinfunction "2_2") (pintype "passive"))
      (node (ref "R95") (pin "1") (pinfunction "1_1") (pintype "passive"))
    )
    (net (code "71") (name "Net-(IC10C--IN)") (class "Default")
      (node (ref "C46") (pin "2") (pinfunction "2_2") (pintype "passive"))
      (node (ref "D12") (pin "A") (pinfunction "A_A") (pintype "passive"))
      (node (ref "IC10") (pin "9") (pinfunction "-IN_9") (pintype "input"))
      (node (ref "R65") (pin "P$1") (pinfunction "E_P$1") (pintype "passive"))
      (node (ref "R93") (pin "1") (pinfunction "1_1") (pintype "passive"))
      (node (ref "R95") (pin "2") (pinfunction "2_2") (pintype "passive"))
    )
    (net (code "72") (name "Net-(IC10C-OUT)") (class "Default")
      (node (ref "D12") (pin "C") (pinfunction "C_C") (pintype "passive"))
      (node (ref "D17") (pin "A") (pinfunction "A_A") (pintype "passive"))
      (node (ref "IC10") (pin "8") (pinfunction "OUT_8") (pintype "output"))
    )
    (net (code "73") (name "Net-(IC10D--IN)") (class "Default")
      (node (ref "C39") (pin "2") (pinfunction "2_2") (pintype "passive"))
      (node (ref "D11") (pin "A") (pinfunction "A_A") (pintype "passive"))
      (node (ref "IC10") (pin "13") (pinfunction "-IN_13") (pintype "input"))
      (node (ref "R68") (pin "P$3") (pinfunction "A_P$3") (pintype "passive"))
      (node (ref "R81") (pin "2") (pinfunction "2_2") (pintype "passive"))
      (node (ref "R82") (pin "2") (pinfunction "2_2") (pintype "passive"))
      (node (ref "R85") (pin "1") (pinfunction "1_1") (pintype "passive"))
    )
    (net (code "74") (name "Net-(IC10D-OUT)") (class "Default")
      (node (ref "D11") (pin "C") (pinfunction "C_C") (pintype "passive"))
      (node (ref "D16") (pin "A") (pinfunction "A_A") (pintype "passive"))
      (node (ref "IC10") (pin "14") (pinfunction "OUT_14") (pintype "output"))
    )
    (net (code "75") (name "Net-(IC11A-CTRL)") (class "Default")
      (node (ref "C39") (pin "1") (pinfunction "1_1") (pintype "passive"))
      (node (ref "D16") (pin "C") (pinfunction "C_C") (pintype "passive"))
      (node (ref "IC11") (pin "14") (pinfunction "CTRL_14") (pintype "input"))
      (node (ref "IC11") (pin "3") (pinfunction "CTRL_3") (pintype "input"))
      (node (ref "R85") (pin "2") (pinfunction "2_2") (pintype "passive"))
    )
    (net (code "76") (name "Net-(IC11A-IN)") (class "Default")
      (node (ref "IC11") (pin "2") (pinfunction "IN_2") (pintype "input"))
      (node (ref "R86") (pin "2") (pinfunction "2_2") (pintype "passive"))
      (node (ref "R89") (pin "2") (pinfunction "2_2") (pintype "passive"))
    )
    (net (code "77") (name "Net-(IC11A-OUT)") (class "Default")
      (node (ref "C40") (pin "1") (pinfunction "1_1") (pintype "passive"))
      (node (ref "IC11") (pin "4") (pinfunction "OUT_4") (pintype "output"))
      (node (ref "IC9") (pin "6") (pinfunction "-IN_6") (pintype "input"))
    )
    (net (code "78") (name "Net-(IC11B-CTRL)") (class "Default")
      (node (ref "C46") (pin "1") (pinfunction "1_1") (pintype "passive"))
      (node (ref "D17") (pin "C") (pinfunction "C_C") (pintype "passive"))
      (node (ref "IC11") (pin "6") (pinfunction "CTRL_6") (pintype "input"))
      (node (ref "R93") (pin "2") (pinfunction "2_2") (pintype "passive"))
    )
    (net (code "79") (name "Net-(IC11B-IN)") (class "Default")
      (node (ref "IC11") (pin "7") (pinfunction "IN_7") (pintype "input"))
      (node (ref "R94") (pin "2") (pinfunction "2_2") (pintype "passive"))
      (node (ref "R98") (pin "2") (pinfunction "2_2") (pintype "passive"))
    )
    (net (code "80") (name "Net-(IC11B-OUT)") (class "Default")
      (node (ref "IC11") (pin "5") (pinfunction "OUT_5") (pintype "output"))
      (node (ref "IC9") (pin "13") (pinfunction "-IN_13") (pintype "input"))
      (node (ref "R76") (pin "2") (pinfunction "2_2") (pintype "passive"))
    )
    (net (code "81") (name "Net-(IC11C-IN)") (class "Default")
      (node (ref "IC11") (pin "10") (pinfunction "IN_10") (pintype "input"))
      (node (ref "R97") (pin "2") (pinfunction "2_2") (pintype "passive"))
      (node (ref "R99") (pin "2") (pinfunction "2_2") (pintype "passive"))
    )
    (net (code "82") (name "Net-(IC11D-IN)") (class "Default")
      (node (ref "IC11") (pin "15") (pinfunction "IN_15") (pintype "input"))
      (node (ref "R87") (pin "2") (pinfunction "2_2") (pintype "passive"))
      (node (ref "R90") (pin "2") (pinfunction "2_2") (pintype "passive"))
    )
    (net (code "83") (name "Net-(IC11D-OUT)") (class "Default")
      (node (ref "C41") (pin "1") (pinfunction "1_1") (pintype "passive"))
      (node (ref "IC11") (pin "13") (pinfunction "OUT_13") (pintype "output"))
      (node (ref "IC9") (pin "9") (pinfunction "-IN_9") (pintype "input"))
    )
    (net (code "84") (name "Net-(IC12A--IN)") (class "Default")
      (node (ref "IC12") (pin "2") (pinfunction "-IN_2") (pintype "input"))
      (node (ref "R102") (pin "1") (pinfunction "1_1") (pintype "passive"))
      (node (ref "R105") (pin "2") (pinfunction "2_2") (pintype "passive"))
    )
    (net (code "85") (name "Net-(IC12A-OUT)") (class "Default")
      (node (ref "IC12") (pin "1") (pinfunction "OUT_1") (pintype "output"))
      (node (ref "R102") (pin "2") (pinfunction "2_2") (pintype "passive"))
      (node (ref "R106") (pin "1") (pinfunction "1_1") (pintype "passive"))
    )
    (net (code "86") (name "Net-(IC12B--IN)") (class "Default")
      (node (ref "IC12") (pin "6") (pinfunction "-IN_6") (pintype "input"))
      (node (ref "R103") (pin "1") (pinfunction "1_1") (pintype "passive"))
      (node (ref "R106") (pin "2") (pinfunction "2_2") (pintype "passive"))
      (node (ref "R122") (pin "1") (pinfunction "1_1") (pintype "passive"))
    )
    (net (code "87") (name "Net-(IC13B-OUT)") (class "Default")
      (node (ref "IC13") (pin "7") (pinfunction "OUT_7") (pintype "output"))
      (node (ref "R104") (pin "1") (pinfunction "1_1") (pintype "passive"))
      (node (ref "R110") (pin "2") (pinfunction "2_2") (pintype "passive"))
    )
    (net (code "88") (name "Net-(IC14A-+IN)") (class "Default")
      (node (ref "IC14") (pin "3") (pinfunction "+IN_3") (pintype "input"))
      (node (ref "IC14") (pin "6") (pinfunction "-IN_6") (pintype "input"))
      (node (ref "R115") (pin "2") (pinfunction "2_2") (pintype "passive"))
      (node (ref "R117") (pin "2") (pinfunction "2_2") (pintype "passive"))
      (node (ref "R118") (pin "1") (pinfunction "1_1") (pintype "passive"))
    )
    (net (code "89") (name "Net-(IC14A--IN)") (class "Default")
      (node (ref "IC14") (pin "2") (pinfunction "-IN_2") (pintype "input"))
      (node (ref "R119") (pin "2") (pinfunction "2_2") (pintype "passive"))
      (node (ref "R121") (pin "1") (pinfunction "1_1") (pintype "passive"))
    )
    (net (code "90") (name "Net-(IC14A-OUT)") (class "Default")
      (node (ref "D13") (pin "A") (pinfunction "A_A") (pintype "passive"))
      (node (ref "IC14") (pin "1") (pinfunction "OUT_1") (pintype "output"))
    )
    (net (code "91") (name "Net-(IC14B-+IN)") (class "Default")
      (node (ref "IC14") (pin "5") (pinfunction "+IN_5") (pintype "input"))
      (node (ref "R119") (pin "1") (pinfunction "1_1") (pintype "passive"))
      (node (ref "R120") (pin "2") (pinfunction "2_2") (pintype "passive"))
    )
    (net (code "92") (name "Net-(IC14B-OUT)") (class "Default")
      (node (ref "D14") (pin "A") (pinfunction "A_A") (pintype "passive"))
      (node (ref "IC14") (pin "7") (pinfunction "OUT_7") (pintype "output"))
    )
    (net (code "93") (name "Net-(J1-3)") (class "Default")
      (node (ref "J1") (pin "P3") (pinfunction "3_P3") (pintype "passive"))
      (node (ref "R6") (pin "1") (pinfunction "1_1") (pintype "passive"))
    )
    (net (code "94") (name "Net-(J2-3)") (class "Default")
      (node (ref "J2") (pin "P3") (pinfunction "3_P3") (pintype "passive"))
      (node (ref "R30") (pin "1") (pinfunction "1_1") (pintype "passive"))
    )
    (net (code "95") (name "Net-(J3-3)") (class "Default")
      (node (ref "J3") (pin "P3") (pinfunction "3_P3") (pintype "passive"))
      (node (ref "R48") (pin "1") (pinfunction "1_1") (pintype "passive"))
    )
    (net (code "96") (name "Net-(J4-3)") (class "Default")
      (node (ref "J4") (pin "P3") (pinfunction "3_P3") (pintype "passive"))
      (node (ref "R45") (pin "1") (pinfunction "1_1") (pintype "passive"))
    )
    (net (code "97") (name "Net-(J5-3)") (class "Default")
      (node (ref "J5") (pin "P3") (pinfunction "3_P3") (pintype "passive"))
      (node (ref "R58") (pin "1") (pinfunction "1_1") (pintype "passive"))
    )
    (net (code "98") (name "Net-(J6-3)") (class "Default")
      (node (ref "J6") (pin "P3") (pinfunction "3_P3") (pintype "passive"))
      (node (ref "R91") (pin "1") (pinfunction "1_1") (pintype "passive"))
    )
    (net (code "99") (name "Net-(J7-3)") (class "Default")
      (node (ref "J7") (pin "P3") (pinfunction "3_P3") (pintype "passive"))
      (node (ref "R82") (pin "1") (pinfunction "1_1") (pintype "passive"))
    )
    (net (code "100") (name "Net-(J8-3)") (class "Default")
      (node (ref "J8") (pin "P3") (pinfunction "3_P3") (pintype "passive"))
      (node (ref "R78") (pin "1") (pinfunction "1_1") (pintype "passive"))
    )
    (net (code "101") (name "Net-(J9-3)") (class "Default")
      (node (ref "J9") (pin "P3") (pinfunction "3_P3") (pintype "passive"))
      (node (ref "R9") (pin "1") (pinfunction "1_1") (pintype "passive"))
    )
    (net (code "102") (name "Net-(J10-3)") (class "Default")
      (node (ref "J10") (pin "P3") (pinfunction "3_P3") (pintype "passive"))
      (node (ref "R27") (pin "1") (pinfunction "1_1") (pintype "passive"))
    )
    (net (code "103") (name "Net-(J13-3)") (class "Default")
      (node (ref "J13") (pin "P3") (pinfunction "3_P3") (pintype "passive"))
      (node (ref "R105") (pin "1") (pinfunction "1_1") (pintype "passive"))
    )
    (net (code "104") (name "Net-(J14-3)") (class "Default")
      (node (ref "J14") (pin "P3") (pinfunction "3_P3") (pintype "passive"))
      (node (ref "R111") (pin "2") (pinfunction "2_2") (pintype "passive"))
    )
    (net (code "105") (name "Net-(J15-3)") (class "Default")
      (node (ref "J15") (pin "P3") (pinfunction "3_P3") (pintype "passive"))
      (node (ref "R123") (pin "2") (pinfunction "2_2") (pintype "passive"))
    )
    (net (code "106") (name "Net-(J16-3)") (class "Default")
      (node (ref "J16") (pin "P3") (pinfunction "3_P3") (pintype "passive"))
      (node (ref "R124") (pin "2") (pinfunction "2_2") (pintype "passive"))
    )
    (net (code "107") (name "Net-(J17-3)") (class "Default")
      (node (ref "J17") (pin "P3") (pinfunction "3_P3") (pintype "passive"))
      (node (ref "R125") (pin "2") (pinfunction "2_2") (pintype "passive"))
    )
    (net (code "108") (name "Net-(J18-3)") (class "Default")
      (node (ref "J18") (pin "P3") (pinfunction "3_P3") (pintype "passive"))
      (node (ref "R126") (pin "2") (pinfunction "2_2") (pintype "passive"))
    )
    (net (code "109") (name "Net-(J19-3)") (class "Default")
      (node (ref "J19") (pin "P3") (pinfunction "3_P3") (pintype "passive"))
      (node (ref "R127") (pin "2") (pinfunction "2_2") (pintype "passive"))
    )
    (net (code "110") (name "Net-(J20-3)") (class "Default")
      (node (ref "J20") (pin "P3") (pinfunction "3_P3") (pintype "passive"))
      (node (ref "R128") (pin "2") (pinfunction "2_2") (pintype "passive"))
    )
    (net (code "111") (name "Net-(JP5-Pad2)") (class "Default")
      (node (ref "JP5") (pin "2") (pinfunction "2_2") (pintype "passive"))
      (node (ref "R122") (pin "2") (pinfunction "2_2") (pintype "passive"))
    )
    (net (code "112") (name "Net-(JP11-Pad10)") (class "Default")
      (node (ref "JP11") (pin "10") (pinfunction "10_10") (pintype "passive"))
      (node (ref "JP11") (pin "9") (pinfunction "9_9") (pintype "passive"))
      (node (ref "P1") (pin "2") (pinfunction "2_2") (pintype "bidirectional"))
    )
    (net (code "113") (name "Net-(LED1-C)") (class "Default")
      (node (ref "LED1") (pin "K") (pinfunction "C_K") (pintype "passive"))
      (node (ref "Q1") (pin "C") (pinfunction "C_C") (pintype "passive"))
    )
    (net (code "114") (name "Net-(LED1-PadA)") (class "Default")
      (node (ref "LED1") (pin "A") (pinfunction "A_A") (pintype "passive"))
      (node (ref "R112") (pin "1") (pinfunction "1_1") (pintype "passive"))
    )
    (net (code "115") (name "Net-(Q1-PadB)") (class "Default")
      (node (ref "Q1") (pin "B") (pinfunction "B_B") (pintype "passive"))
      (node (ref "R114") (pin "2") (pinfunction "2_2") (pintype "passive"))
      (node (ref "R116") (pin "2") (pinfunction "2_2") (pintype "passive"))
    )
    (net (code "116") (name "Net-(R3-S)") (class "Default")
      (node (ref "R3") (pin "P$2") (pinfunction "S_P$2") (pintype "passive"))
      (node (ref "R5") (pin "2") (pinfunction "2_2") (pintype "passive"))
    )
    (net (code "117") (name "Net-(R4-S)") (class "Default")
      (node (ref "R12") (pin "2") (pinfunction "2_2") (pintype "passive"))
      (node (ref "R4") (pin "P$2") (pinfunction "S_P$2") (pintype "passive"))
    )
    (net (code "118") (name "Net-(R34-S)") (class "Default")
      (node (ref "R34") (pin "P$2") (pinfunction "S_P$2") (pintype "passive"))
      (node (ref "R43") (pin "2") (pinfunction "2_2") (pintype "passive"))
    )
    (net (code "119") (name "Net-(R36-S)") (class "Default")
      (node (ref "R36") (pin "P$2") (pinfunction "S_P$2") (pintype "passive"))
      (node (ref "R49") (pin "2") (pinfunction "2_2") (pintype "passive"))
    )
    (net (code "120") (name "Net-(R39-Pad2)") (class "Default")
      (node (ref "R39") (pin "2") (pinfunction "2_2") (pintype "passive"))
      (node (ref "R41") (pin "1") (pinfunction "1_1") (pintype "passive"))
    )
    (net (code "121") (name "Net-(R42-S)") (class "Default")
      (node (ref "R42") (pin "P$2") (pinfunction "S_P$2") (pintype "passive"))
      (node (ref "R54") (pin "2") (pinfunction "2_2") (pintype "passive"))
    )
    (net (code "122") (name "Net-(R65-S)") (class "Default")
      (node (ref "R65") (pin "P$2") (pinfunction "S_P$2") (pintype "passive"))
      (node (ref "R70") (pin "2") (pinfunction "2_2") (pintype "passive"))
    )
    (net (code "123") (name "Net-(R68-S)") (class "Default")
      (node (ref "R68") (pin "P$2") (pinfunction "S_P$2") (pintype "passive"))
      (node (ref "R77") (pin "2") (pinfunction "2_2") (pintype "passive"))
    )
    (net (code "124") (name "Net-(R69-S)") (class "Default")
      (node (ref "R69") (pin "P$2") (pinfunction "S_P$2") (pintype "passive"))
      (node (ref "R83") (pin "2") (pinfunction "2_2") (pintype "passive"))
    )
    (net (code "125") (name "Net-(R74-Pad2)") (class "Default")
      (node (ref "R74") (pin "2") (pinfunction "2_2") (pintype "passive"))
      (node (ref "R76") (pin "1") (pinfunction "1_1") (pintype "passive"))
    )
    (net (code "126") (name "Net-(R100-S)") (class "Default")
      (node (ref "R100") (pin "P$2") (pinfunction "S_P$2") (pintype "passive"))
      (node (ref "R109") (pin "2") (pinfunction "2_2") (pintype "passive"))
    )
    (net (code "127") (name "Net-(R101-S)") (class "Default")
      (node (ref "R101") (pin "P$2") (pinfunction "S_P$2") (pintype "passive"))
      (node (ref "R108") (pin "2") (pinfunction "2_2") (pintype "passive"))
    )
    (net (code "128") (name "OUTPUT") (class "Default")
      (node (ref "C57") (pin "2") (pinfunction "2_2") (pintype "passive"))
      (node (ref "IC13") (pin "1") (pinfunction "OUT_1") (pintype "output"))
      (node (ref "R107") (pin "2") (pinfunction "2_2") (pintype "passive"))
      (node (ref "R111") (pin "1") (pinfunction "1_1") (pintype "passive"))
    )
    (net (code "129") (name "PLUS_BUS") (class "Default")
      (node (ref "IC13") (pin "6") (pinfunction "-IN_6") (pintype "input"))
      (node (ref "IC5") (pin "12") (pinfunction "OUT_12") (pintype "output"))
      (node (ref "R110") (pin "1") (pinfunction "1_1") (pintype "passive"))
      (node (ref "R33") (pin "2") (pinfunction "2_2") (pintype "passive"))
      (node (ref "R55") (pin "2") (pinfunction "2_2") (pintype "passive"))
      (node (ref "R88") (pin "2") (pinfunction "2_2") (pintype "passive"))
    )
    (net (code "130") (name "VCC") (class "Default")
      (node (ref "C1") (pin "+") (pinfunction "+_+") (pintype "passive"))
      (node (ref "C12") (pin "1") (pinfunction "1_1") (pintype "passive"))
      (node (ref "C21") (pin "1") (pinfunction "1_1") (pintype "passive"))
      (node (ref "C27") (pin "1") (pinfunction "1_1") (pintype "passive"))
      (node (ref "C31") (pin "1") (pinfunction "1_1") (pintype "passive"))
      (node (ref "C36") (pin "1") (pinfunction "1_1") (pintype "passive"))
      (node (ref "C42") (pin "1") (pinfunction "1_1") (pintype "passive"))
      (node (ref "C43") (pin "1") (pinfunction "1_1") (pintype "passive"))
      (node (ref "C5") (pin "1") (pinfunction "1_1") (pintype "passive"))
      (node (ref "C50") (pin "1") (pinfunction "1_1") (pintype "passive"))
      (node (ref "C52") (pin "1") (pinfunction "1_1") (pintype "passive"))
      (node (ref "C56") (pin "1") (pinfunction "1_1") (pintype "passive"))
      (node (ref "C58") (pin "+") (pinfunction "+_+") (pintype "passive"))
      (node (ref "C9") (pin "1") (pinfunction "1_1") (pintype "passive"))
      (node (ref "D2") (pin "C") (pinfunction "C_C") (pintype "passive"))
      (node (ref "IC10") (pin "4") (pinfunction "V+_4") (pintype "power_in"))
      (node (ref "IC11") (pin "16") (pinfunction "V+_16") (pintype "power_in"))
      (node (ref "IC12") (pin "8") (pinfunction "V+_8") (pintype "power_in"))
      (node (ref "IC13") (pin "8") (pinfunction "V+_8") (pintype "power_in"))
      (node (ref "IC14") (pin "8") (pinfunction "V+_8") (pintype "power_in"))
      (node (ref "IC3") (pin "8") (pinfunction "V+_8") (pintype "power_in"))
      (node (ref "IC4") (pin "4") (pinfunction "V+_4") (pintype "power_in"))
      (node (ref "IC5") (pin "16") (pinfunction "V+_16") (pintype "power_in"))
      (node (ref "IC6") (pin "4") (pinfunction "V+_4") (pintype "power_in"))
      (node (ref "IC7") (pin "4") (pinfunction "V+_4") (pintype "power_in"))
      (node (ref "IC8") (pin "16") (pinfunction "V+_16") (pintype "power_in"))
      (node (ref "IC9") (pin "4") (pinfunction "V+_4") (pintype "power_in"))
      (node (ref "R1") (pin "1") (pinfunction "1_1") (pintype "passive"))
      (node (ref "R112") (pin "2") (pinfunction "2_2") (pintype "passive"))
    )
    (net (code "131") (name "VEE") (class "Default")
      (node (ref "C13") (pin "2") (pinfunction "2_2") (pintype "passive"))
      (node (ref "C2") (pin "-") (pinfunction "-_-") (pintype "passive"))
      (node (ref "C20") (pin "2") (pinfunction "2_2") (pintype "passive"))
      (node (ref "C22") (pin "2") (pinfunction "2_2") (pintype "passive"))
      (node (ref "C28") (pin "2") (pinfunction "2_2") (pintype "passive"))
      (node (ref "C35") (pin "2") (pinfunction "2_2") (pintype "passive"))
      (node (ref "C37") (pin "2") (pinfunction "2_2") (pintype "passive"))
      (node (ref "C44") (pin "2") (pinfunction "2_2") (pintype "passive"))
      (node (ref "C51") (pin "2") (pinfunction "2_2") (pintype "passive"))
      (node (ref "C53") (pin "2") (pinfunction "2_2") (pintype "passive"))
      (node (ref "C54") (pin "2") (pinfunction "2_2") (pintype "passive"))
      (node (ref "C8") (pin "2") (pinfunction "2_2") (pintype "passive"))
      (node (ref "D1") (pin "A") (pinfunction "A_A") (pintype "passive"))
      (node (ref "IC10") (pin "11") (pinfunction "V-_11") (pintype "power_in"))
      (node (ref "IC11") (pin "9") (pinfunction "V-_9") (pintype "power_in"))
      (node (ref "IC12") (pin "4") (pinfunction "V-_4") (pintype "power_in"))
      (node (ref "IC13") (pin "4") (pinfunction "V-_4") (pintype "power_in"))
      (node (ref "IC3") (pin "4") (pinfunction "V-_4") (pintype "power_in"))
      (node (ref "IC4") (pin "11") (pinfunction "V-_11") (pintype "power_in"))
      (node (ref "IC5") (pin "9") (pinfunction "V-_9") (pintype "power_in"))
      (node (ref "IC6") (pin "11") (pinfunction "V-_11") (pintype "power_in"))
      (node (ref "IC7") (pin "11") (pinfunction "V-_11") (pintype "power_in"))
      (node (ref "IC8") (pin "9") (pinfunction "V-_9") (pintype "power_in"))
      (node (ref "IC9") (pin "11") (pinfunction "V-_11") (pintype "power_in"))
      (node (ref "P1") (pin "1") (pinfunction "1_1") (pintype "bidirectional"))
      (node (ref "R2") (pin "1") (pinfunction "1_1") (pintype "passive"))
    )
    (net (code "132") (name "unconnected-(IC5E-MODE-Pad1)") (class "Default")
      (node (ref "IC5") (pin "1") (pinfunction "MODE_1") (pintype "input"))
    )
    (net (code "133") (name "unconnected-(IC8E-MODE-Pad1)") (class "Default")
      (node (ref "IC8") (pin "1") (pinfunction "MODE_1") (pintype "input"))
    )
    (net (code "134") (name "unconnected-(IC11E-MODE-Pad1)") (class "Default")
      (node (ref "IC11") (pin "1") (pinfunction "MODE_1") (pintype "input"))
    )
    (net (code "135") (name "unconnected-(J1-2-PadP2)") (class "Default")
      (node (ref "J1") (pin "P2") (pinfunction "2_P2") (pintype "passive"))
    )
    (net (code "136") (name "unconnected-(J2-2-PadP2)") (class "Default")
      (node (ref "J2") (pin "P2") (pinfunction "2_P2") (pintype "passive"))
    )
    (net (code "137") (name "unconnected-(J3-2-PadP2)") (class "Default")
      (node (ref "J3") (pin "P2") (pinfunction "2_P2") (pintype "passive"))
    )
    (net (code "138") (name "unconnected-(J4-2-PadP2)") (class "Default")
      (node (ref "J4") (pin "P2") (pinfunction "2_P2") (pintype "passive"))
    )
    (net (code "139") (name "unconnected-(J5-2-PadP2)") (class "Default")
      (node (ref "J5") (pin "P2") (pinfunction "2_P2") (pintype "passive"))
    )
    (net (code "140") (name "unconnected-(J6-2-PadP2)") (class "Default")
      (node (ref "J6") (pin "P2") (pinfunction "2_P2") (pintype "passive"))
    )
    (net (code "141") (name "unconnected-(J7-2-PadP2)") (class "Default")
      (node (ref "J7") (pin "P2") (pinfunction "2_P2") (pintype "passive"))
    )
    (net (code "142") (name "unconnected-(J8-2-PadP2)") (class "Default")
      (node (ref "J8") (pin "P2") (pinfunction "2_P2") (pintype "passive"))
    )
    (net (code "143") (name "unconnected-(J9-2-PadP2)") (class "Default")
      (node (ref "J9") (pin "P2") (pinfunction "2_P2") (pintype "passive"))
    )
    (net (code "144") (name "unconnected-(J10-2-PadP2)") (class "Default")
      (node (ref "J10") (pin "P2") (pinfunction "2_P2") (pintype "passive"))
    )
    (net (code "145") (name "unconnected-(J11-2-PadP2)") (class "Default")
      (node (ref "J11") (pin "P2") (pinfunction "2_P2") (pintype "passive"))
    )
    (net (code "146") (name "unconnected-(J12-2-PadP2)") (class "Default")
      (node (ref "J12") (pin "P2") (pinfunction "2_P2") (pintype "passive"))
    )
    (net (code "147") (name "unconnected-(J13-2-PadP2)") (class "Default")
      (node (ref "J13") (pin "P2") (pinfunction "2_P2") (pintype "passive"))
    )
    (net (code "148") (name "unconnected-(J14-2-PadP2)") (class "Default")
      (node (ref "J14") (pin "P2") (pinfunction "2_P2") (pintype "passive"))
    )
    (net (code "149") (name "unconnected-(J15-2-PadP2)") (class "Default")
      (node (ref "J15") (pin "P2") (pinfunction "2_P2") (pintype "passive"))
    )
    (net (code "150") (name "unconnected-(J16-2-PadP2)") (class "Default")
      (node (ref "J16") (pin "P2") (pinfunction "2_P2") (pintype "passive"))
    )
    (net (code "151") (name "unconnected-(J17-2-PadP2)") (class "Default")
      (node (ref "J17") (pin "P2") (pinfunction "2_P2") (pintype "passive"))
    )
    (net (code "152") (name "unconnected-(J18-2-PadP2)") (class "Default")
      (node (ref "J18") (pin "P2") (pinfunction "2_P2") (pintype "passive"))
    )
    (net (code "153") (name "unconnected-(J19-2-PadP2)") (class "Default")
      (node (ref "J19") (pin "P2") (pinfunction "2_P2") (pintype "passive"))
    )
    (net (code "154") (name "unconnected-(J20-2-PadP2)") (class "Default")
      (node (ref "J20") (pin "P2") (pinfunction "2_P2") (pintype "passive"))
    )
    (net (code "155") (name "unconnected-(JP5-Pad1)") (class "Default")
      (node (ref "JP5") (pin "1") (pinfunction "1_1") (pintype "passive"))
    )
  )
)
